# MCU.net
KiCad netlist of a schematic drawn in Altium Designer
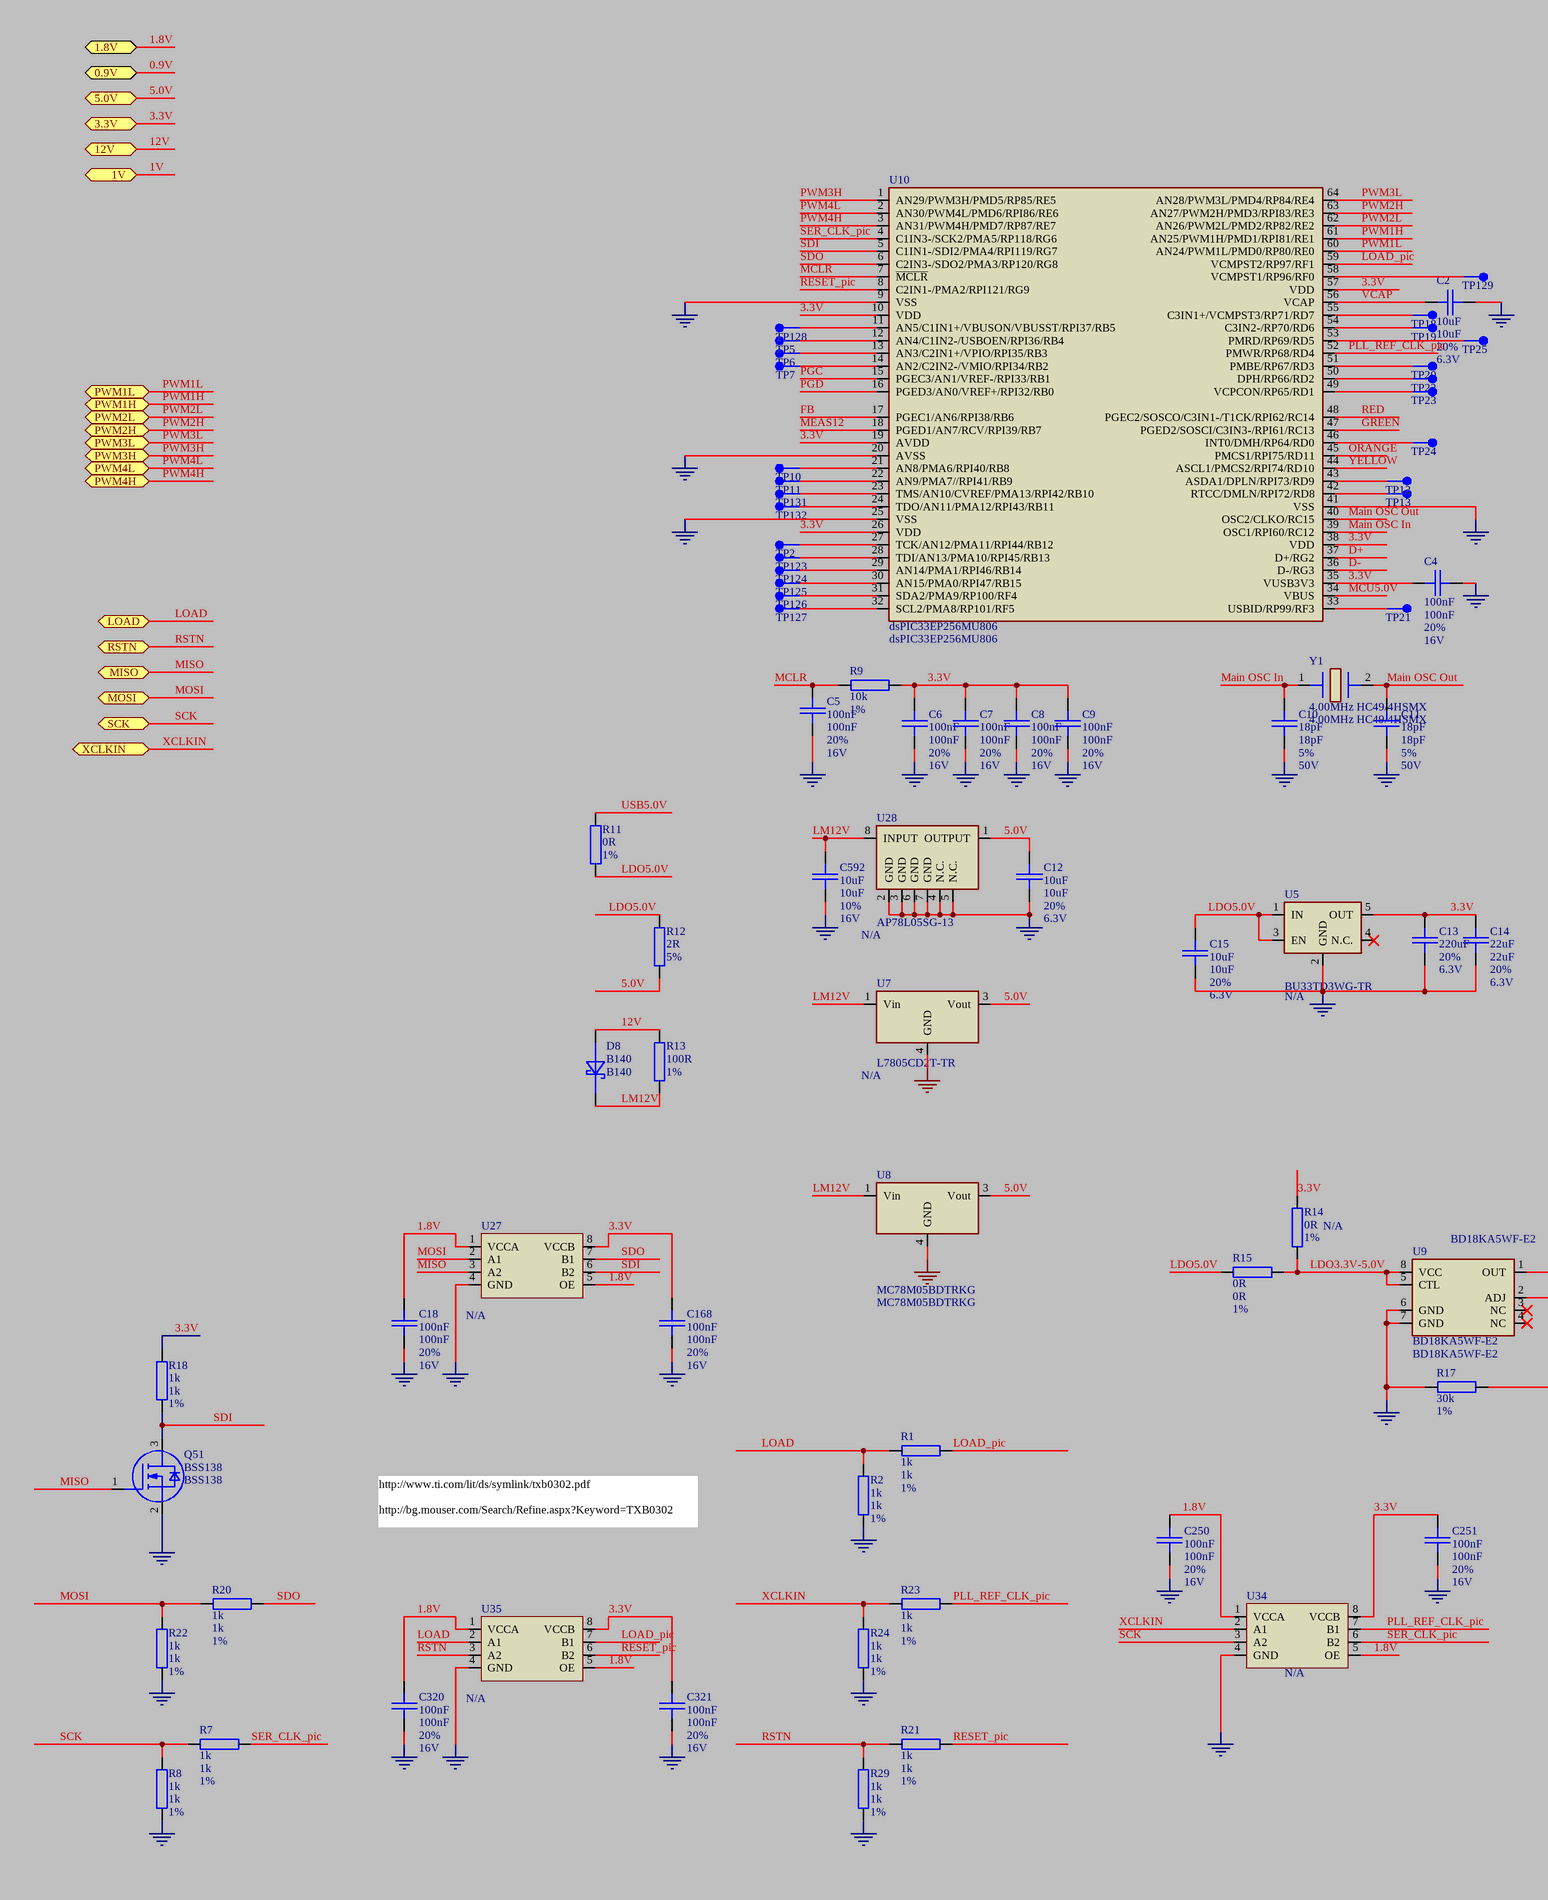
[diagram p0: MCU.SchDoc, left]
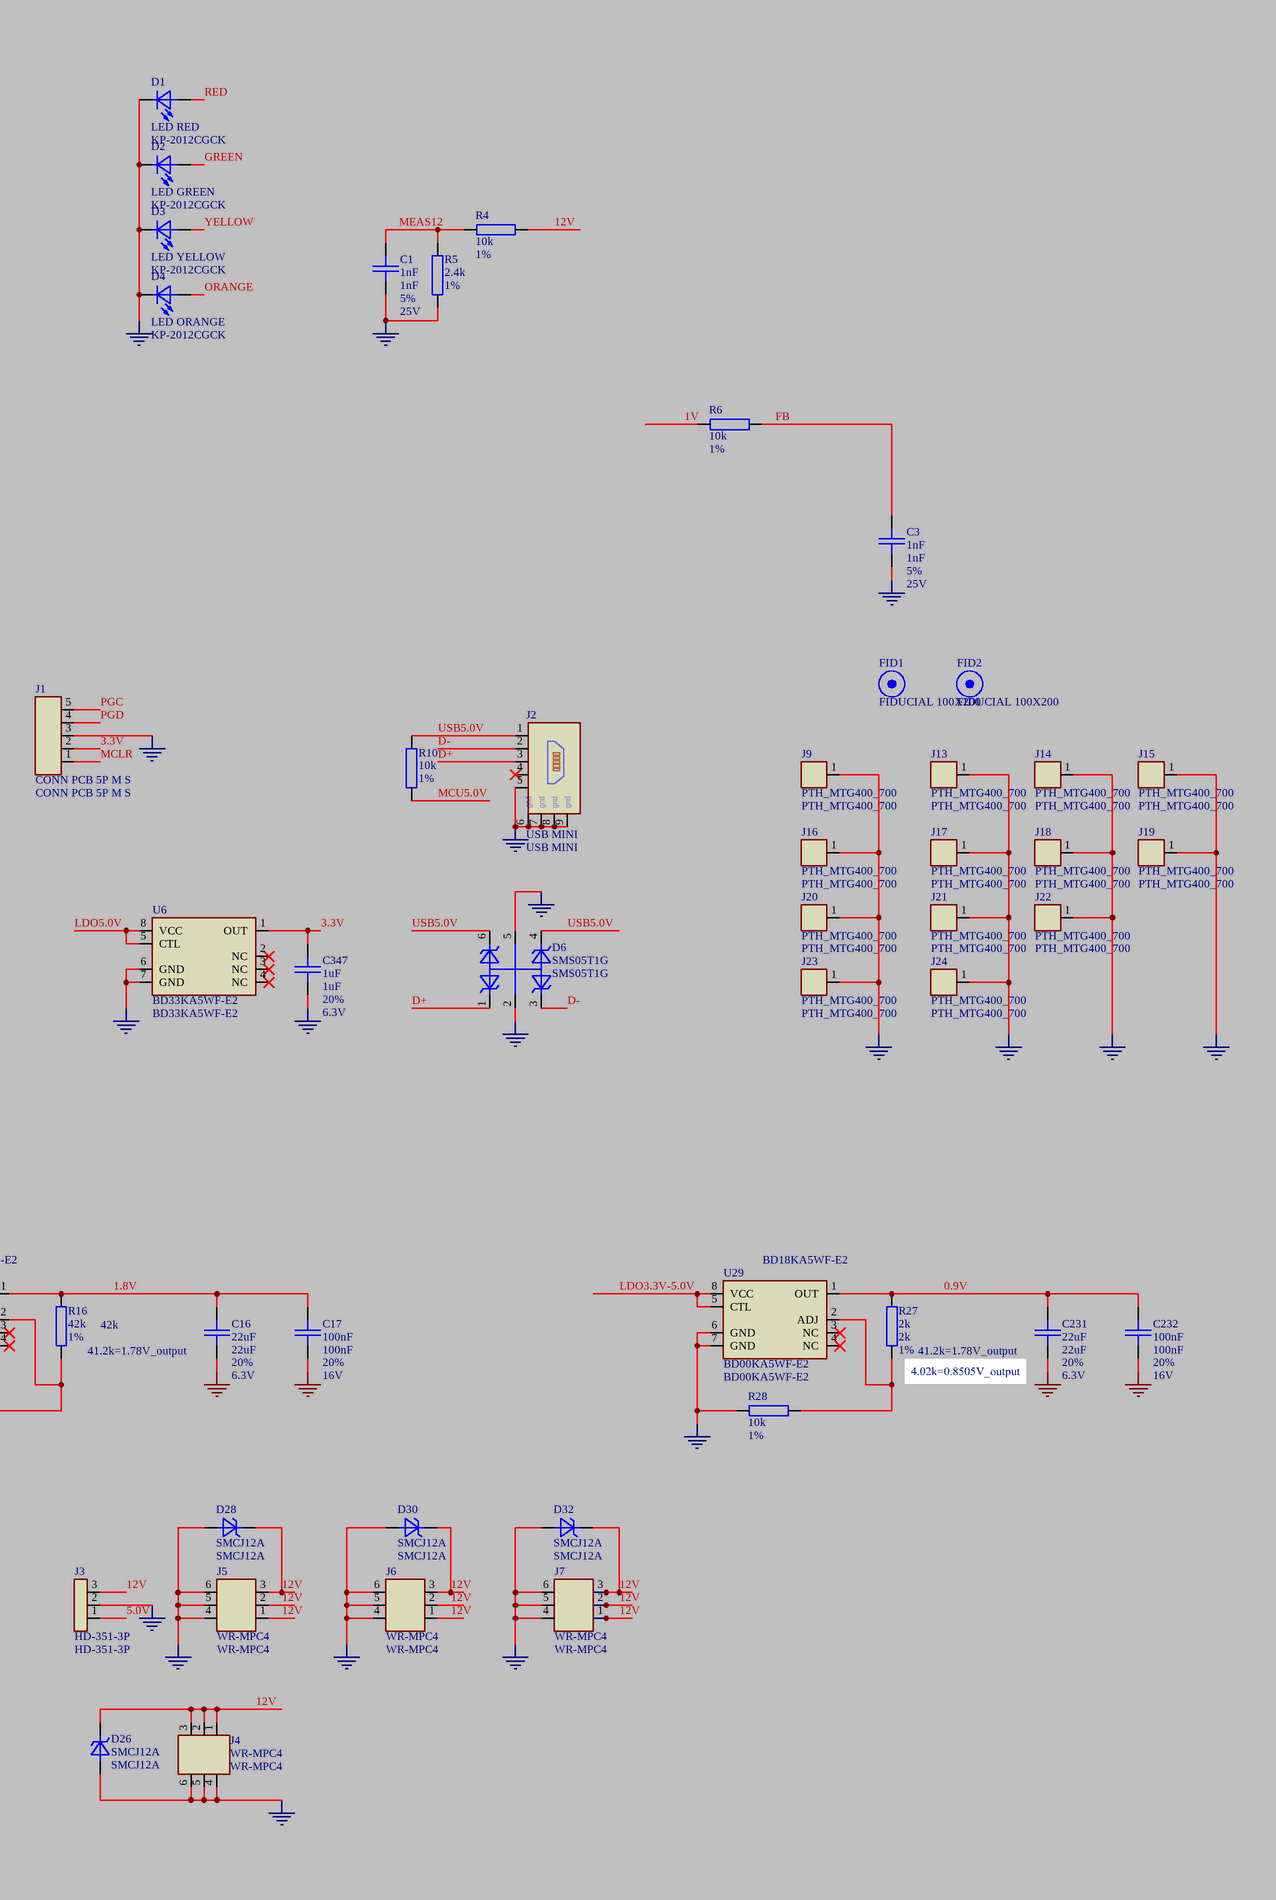
[diagram p1: MCU.SchDoc, right]

(export (version "E")
  (design (tool "Eeschema 10.0.6"))
  (components
    (comp (ref "C1")
      (value "1nF")
      (footprint "SMD_0603_CAPC1608X95N")
      (fields
        (field (name "DB_PART_NUMBER") "CAP000024113")
        (field (name "DB_VALUE") "1nF")
        (field (name "DB_TOLERANCE") "5%")
        (field (name "DB_VOLTAGE") "25V")
        (field (name "DB_MANUFACTURER_PART") "KEMET    C0603C102J3RAC")
        (field (name "DB_APPROVED_BY") "ISHIDDEN=T")
      )
      (libsource (lib "Database_Libs1") (part "C"))
    )
    (comp (ref "C2")
      (value "10uF")
      (footprint "SMD_0603_CAPC1608X95N")
      (fields
        (field (name "DB_PART_NUMBER") "CAP000043646")
        (field (name "DB_VALUE") "10uF")
        (field (name "DB_TOLERANCE") "20%")
        (field (name "DB_VOLTAGE") "6.3V")
        (field (name "DB_MANUFACTURER_PART") "KEMET    C0603C106M9PAC")
        (field (name "DB_APPROVED_BY") "ISHIDDEN=T")
      )
      (libsource (lib "Database_Libs1") (part "C"))
    )
    (comp (ref "C3")
      (value "1nF")
      (footprint "SMD_0603_CAPC1608X95N")
      (fields
        (field (name "DB_PART_NUMBER") "CAP000024113")
        (field (name "DB_VALUE") "1nF")
        (field (name "DB_TOLERANCE") "5%")
        (field (name "DB_VOLTAGE") "25V")
        (field (name "DB_MANUFACTURER_PART") "KEMET    C0603C102J3RAC")
        (field (name "DB_APPROVED_BY") "ISHIDDEN=T")
      )
      (libsource (lib "Database_Libs1") (part "C"))
    )
    (comp (ref "C4")
      (value "100nF")
      (footprint "SMD_0603_CAPC1608X95N")
      (fields
        (field (name "DB_PART_NUMBER") "CAP000027236")
        (field (name "DB_VALUE") "100nF")
        (field (name "DB_TOLERANCE") "20%")
        (field (name "DB_VOLTAGE") "16V")
        (field (name "DB_MANUFACTURER_PART") "KEMET    C0603C104M4RAC")
        (field (name "DB_APPROVED_BY") "ISHIDDEN=T")
      )
      (libsource (lib "Database_Libs1") (part "C"))
    )
    (comp (ref "C5")
      (value "100nF")
      (footprint "SMD_0603_CAPC1608X95N")
      (fields
        (field (name "DB_PART_NUMBER") "CAP000027236")
        (field (name "DB_VALUE") "100nF")
        (field (name "DB_TOLERANCE") "20%")
        (field (name "DB_VOLTAGE") "16V")
        (field (name "DB_MANUFACTURER_PART") "KEMET    C0603C104M4RAC")
        (field (name "DB_APPROVED_BY") "ISHIDDEN=T")
      )
      (libsource (lib "Database_Libs1") (part "C"))
    )
    (comp (ref "C6")
      (value "100nF")
      (footprint "SMD_0603_CAPC1608X95N")
      (fields
        (field (name "DB_PART_NUMBER") "CAP000027236")
        (field (name "DB_VALUE") "100nF")
        (field (name "DB_TOLERANCE") "20%")
        (field (name "DB_VOLTAGE") "16V")
        (field (name "DB_MANUFACTURER_PART") "KEMET    C0603C104M4RAC")
        (field (name "DB_APPROVED_BY") "ISHIDDEN=T")
      )
      (libsource (lib "Database_Libs1") (part "C"))
    )
    (comp (ref "C7")
      (value "100nF")
      (footprint "SMD_0603_CAPC1608X95N")
      (fields
        (field (name "DB_PART_NUMBER") "CAP000027236")
        (field (name "DB_VALUE") "100nF")
        (field (name "DB_TOLERANCE") "20%")
        (field (name "DB_VOLTAGE") "16V")
        (field (name "DB_MANUFACTURER_PART") "KEMET    C0603C104M4RAC")
        (field (name "DB_APPROVED_BY") "ISHIDDEN=T")
      )
      (libsource (lib "Database_Libs1") (part "C"))
    )
    (comp (ref "C8")
      (value "100nF")
      (footprint "SMD_0603_CAPC1608X95N")
      (fields
        (field (name "DB_PART_NUMBER") "CAP000027236")
        (field (name "DB_VALUE") "100nF")
        (field (name "DB_TOLERANCE") "20%")
        (field (name "DB_VOLTAGE") "16V")
        (field (name "DB_MANUFACTURER_PART") "KEMET    C0603C104M4RAC")
        (field (name "DB_APPROVED_BY") "ISHIDDEN=T")
      )
      (libsource (lib "Database_Libs1") (part "C"))
    )
    (comp (ref "C9")
      (value "100nF")
      (footprint "SMD_0603_CAPC1608X95N")
      (fields
        (field (name "DB_PART_NUMBER") "CAP000027236")
        (field (name "DB_VALUE") "100nF")
        (field (name "DB_TOLERANCE") "20%")
        (field (name "DB_VOLTAGE") "16V")
        (field (name "DB_MANUFACTURER_PART") "KEMET    C0603C104M4RAC")
        (field (name "DB_APPROVED_BY") "ISHIDDEN=T")
      )
      (libsource (lib "Database_Libs1") (part "C"))
    )
    (comp (ref "C10")
      (value "18pF")
      (footprint "SMD_0603_CAPC1608X95N")
      (fields
        (field (name "DB_PART_NUMBER") "CAP000031922")
        (field (name "DB_VALUE") "18pF")
        (field (name "DB_TOLERANCE") "5%")
        (field (name "DB_VOLTAGE") "50V")
        (field (name "DB_MANUFACTURER_PART") "KEMET    C0603C180J5GAC")
        (field (name "DB_APPROVED_BY") "ISHIDDEN=T")
      )
      (libsource (lib "Database_Libs1") (part "C"))
    )
    (comp (ref "C11")
      (value "18pF")
      (footprint "SMD_0603_CAPC1608X95N")
      (fields
        (field (name "DB_PART_NUMBER") "CAP000031922")
        (field (name "DB_VALUE") "18pF")
        (field (name "DB_TOLERANCE") "5%")
        (field (name "DB_VOLTAGE") "50V")
        (field (name "DB_MANUFACTURER_PART") "KEMET    C0603C180J5GAC")
        (field (name "DB_APPROVED_BY") "ISHIDDEN=T")
      )
      (libsource (lib "Database_Libs1") (part "C"))
    )
    (comp (ref "C12")
      (value "10uF")
      (footprint "SMD_0603_CAPC1608X95N")
      (fields
        (field (name "DB_PART_NUMBER") "CAP000043646")
        (field (name "DB_VALUE") "10uF")
        (field (name "DB_TOLERANCE") "20%")
        (field (name "DB_VOLTAGE") "6.3V")
        (field (name "DB_MANUFACTURER_PART") "KEMET    C0603C106M9PAC")
        (field (name "DB_APPROVED_BY") "ISHIDDEN=T")
      )
      (libsource (lib "Database_Libs1") (part "C"))
    )
    (comp (ref "C13")
      (value "220uF")
      (footprint "SMD_1210_CAPC3225X279N")
      (fields
        (field (name "DB_PART_NUMBER") "CAP000047355")
        (field (name "DB_VALUE") "220uF")
        (field (name "DB_TOLERANCE") "20%")
        (field (name "DB_VOLTAGE") "6.3V")
        (field (name "DB_MANUFACTURER_PART") "SAMSUNG    CL32A227MQVNNNE")
        (field (name "DB_APPROVED_BY") "VSN")
      )
      (libsource (lib "Database_Libs1") (part "C"))
    )
    (comp (ref "C14")
      (value "22uF")
      (footprint "SMD_0805_CAPC2012X145N")
      (fields
        (field (name "DB_PART_NUMBER") "CAP000043686")
        (field (name "DB_VALUE") "22uF")
        (field (name "DB_TOLERANCE") "20%")
        (field (name "DB_VOLTAGE") "6.3V")
        (field (name "DB_MANUFACTURER_PART") "KEMET    C0805C226M9PAC")
        (field (name "DB_APPROVED_BY") "ISHIDDEN=T")
      )
      (libsource (lib "Database_Libs1") (part "C"))
    )
    (comp (ref "C15")
      (value "10uF")
      (footprint "SMD_0603_CAPC1608X95N")
      (fields
        (field (name "DB_PART_NUMBER") "CAP000043646")
        (field (name "DB_VALUE") "10uF")
        (field (name "DB_TOLERANCE") "20%")
        (field (name "DB_VOLTAGE") "6.3V")
        (field (name "DB_MANUFACTURER_PART") "KEMET    C0603C106M9PAC")
        (field (name "DB_APPROVED_BY") "ISHIDDEN=T")
      )
      (libsource (lib "Database_Libs1") (part "C"))
    )
    (comp (ref "C16")
      (value "22uF")
      (footprint "SMD_0805_CAPC2012X145N")
      (fields
        (field (name "DB_PART_NUMBER") "CAP000043686")
        (field (name "DB_VALUE") "22uF")
        (field (name "DB_TOLERANCE") "20%")
        (field (name "DB_VOLTAGE") "6.3V")
        (field (name "DB_MANUFACTURER_PART") "KEMET    C0805C226M9PAC")
        (field (name "DB_APPROVED_BY") "ISHIDDEN=T")
      )
      (libsource (lib "Database_Libs1") (part "C"))
    )
    (comp (ref "C17")
      (value "100nF")
      (footprint "SMD_0603_CAPC1608X95N")
      (fields
        (field (name "DB_PART_NUMBER") "CAP000027236")
        (field (name "DB_VALUE") "100nF")
        (field (name "DB_TOLERANCE") "20%")
        (field (name "DB_VOLTAGE") "16V")
        (field (name "DB_MANUFACTURER_PART") "KEMET    C0603C104M4RAC")
        (field (name "DB_APPROVED_BY") "ISHIDDEN=T")
      )
      (libsource (lib "Database_Libs1") (part "C"))
    )
    (comp (ref "C18")
      (value "100nF")
      (footprint "SMD_0603_CAPC1608X95N")
      (fields
        (field (name "DB_PART_NUMBER") "CAP000027236")
        (field (name "DB_VALUE") "100nF")
        (field (name "DB_TOLERANCE") "20%")
        (field (name "DB_VOLTAGE") "16V")
        (field (name "DB_MANUFACTURER_PART") "KEMET    C0603C104M4RAC")
        (field (name "DB_APPROVED_BY") "ISHIDDEN=T")
      )
      (libsource (lib "Database_Libs1") (part "C"))
    )
    (comp (ref "C168")
      (value "100nF")
      (footprint "SMD_0603_CAPC1608X95N")
      (fields
        (field (name "DB_PART_NUMBER") "CAP000027236")
        (field (name "DB_VALUE") "100nF")
        (field (name "DB_TOLERANCE") "20%")
        (field (name "DB_VOLTAGE") "16V")
        (field (name "DB_MANUFACTURER_PART") "KEMET    C0603C104M4RAC")
        (field (name "DB_APPROVED_BY") "ISHIDDEN=T")
      )
      (libsource (lib "Database_Libs1") (part "C"))
    )
    (comp (ref "C231")
      (value "22uF")
      (footprint "SMD_0805_CAPC2012X145N")
      (fields
        (field (name "DB_PART_NUMBER") "CAP000043686")
        (field (name "DB_VALUE") "22uF")
        (field (name "DB_TOLERANCE") "20%")
        (field (name "DB_VOLTAGE") "6.3V")
        (field (name "DB_MANUFACTURER_PART") "KEMET    C0805C226M9PAC")
        (field (name "DB_APPROVED_BY") "ISHIDDEN=T")
      )
      (libsource (lib "Database_Libs1") (part "C"))
    )
    (comp (ref "C232")
      (value "100nF")
      (footprint "SMD_0603_CAPC1608X95N")
      (fields
        (field (name "DB_PART_NUMBER") "CAP000027236")
        (field (name "DB_VALUE") "100nF")
        (field (name "DB_TOLERANCE") "20%")
        (field (name "DB_VOLTAGE") "16V")
        (field (name "DB_MANUFACTURER_PART") "KEMET    C0603C104M4RAC")
        (field (name "DB_APPROVED_BY") "ISHIDDEN=T")
      )
      (libsource (lib "Database_Libs1") (part "C"))
    )
    (comp (ref "C250")
      (value "100nF")
      (footprint "SMD_0603_CAPC1608X95N")
      (fields
        (field (name "DB_PART_NUMBER") "CAP000027236")
        (field (name "DB_VALUE") "100nF")
        (field (name "DB_TOLERANCE") "20%")
        (field (name "DB_VOLTAGE") "16V")
        (field (name "DB_MANUFACTURER_PART") "KEMET    C0603C104M4RAC")
        (field (name "DB_APPROVED_BY") "ISHIDDEN=T")
      )
      (libsource (lib "Database_Libs1") (part "C"))
    )
    (comp (ref "C251")
      (value "100nF")
      (footprint "SMD_0603_CAPC1608X95N")
      (fields
        (field (name "DB_PART_NUMBER") "CAP000027236")
        (field (name "DB_VALUE") "100nF")
        (field (name "DB_TOLERANCE") "20%")
        (field (name "DB_VOLTAGE") "16V")
        (field (name "DB_MANUFACTURER_PART") "KEMET    C0603C104M4RAC")
        (field (name "DB_APPROVED_BY") "ISHIDDEN=T")
      )
      (libsource (lib "Database_Libs1") (part "C"))
    )
    (comp (ref "C320")
      (value "100nF")
      (footprint "SMD_0603_CAPC1608X95N")
      (fields
        (field (name "DB_PART_NUMBER") "CAP000027236")
        (field (name "DB_VALUE") "100nF")
        (field (name "DB_TOLERANCE") "20%")
        (field (name "DB_VOLTAGE") "16V")
        (field (name "DB_MANUFACTURER_PART") "KEMET    C0603C104M4RAC")
        (field (name "DB_APPROVED_BY") "ISHIDDEN=T")
      )
      (libsource (lib "Database_Libs1") (part "C"))
    )
    (comp (ref "C321")
      (value "100nF")
      (footprint "SMD_0603_CAPC1608X95N")
      (fields
        (field (name "DB_PART_NUMBER") "CAP000027236")
        (field (name "DB_VALUE") "100nF")
        (field (name "DB_TOLERANCE") "20%")
        (field (name "DB_VOLTAGE") "16V")
        (field (name "DB_MANUFACTURER_PART") "KEMET    C0603C104M4RAC")
        (field (name "DB_APPROVED_BY") "ISHIDDEN=T")
      )
      (libsource (lib "Database_Libs1") (part "C"))
    )
    (comp (ref "C347")
      (value "1uF")
      (footprint "SMD_0603_CAPC1608X95N")
      (fields
        (field (name "DB_PART_NUMBER") "CAP000043344")
        (field (name "DB_VALUE") "1uF")
        (field (name "DB_TOLERANCE") "20%")
        (field (name "DB_VOLTAGE") "6.3V")
        (field (name "DB_MANUFACTURER_PART") "KEMET    C0603C105M9PAC")
        (field (name "DB_APPROVED_BY") "ISHIDDEN=T")
      )
      (libsource (lib "Database_Libs1") (part "C"))
    )
    (comp (ref "C592")
      (value "10uF")
      (footprint "SMD_0805_CAPC2012X145N")
      (fields
        (field (name "DB_PART_NUMBER") "CAP000043636")
        (field (name "DB_VALUE") "10uF")
        (field (name "DB_TOLERANCE") "10%")
        (field (name "DB_VOLTAGE") "16V")
        (field (name "DB_MANUFACTURER_PART") "KEMET    C0805C106K4PAC")
        (field (name "DB_APPROVED_BY") "ISHIDDEN=T")
      )
      (libsource (lib "Database_Libs1") (part "C"))
    )
    (comp (ref "D1")
      (value "LED RED")
      (footprint "SMD_0805_LED2012X100N")
      (fields
        (field (name "DB_PART_NUMBER") "OPT000000096")
        (field (name "DB_VALUE") "KP-2012CGCK")
        (field (name "DB_MANUFACTURER_PART") "KINGBRIGHT       KP-2012CGCK")
        (field (name "DB_APPROVED_BY") "VSN")
      )
      (libsource (lib "Database_Libs1") (part "LED"))
    )
    (comp (ref "D2")
      (value "LED GREEN")
      (footprint "SMD_0805_LED2012X100N")
      (fields
        (field (name "DB_PART_NUMBER") "OPT000000096")
        (field (name "DB_VALUE") "KP-2012CGCK")
        (field (name "DB_MANUFACTURER_PART") "KINGBRIGHT       KP-2012CGCK")
        (field (name "DB_APPROVED_BY") "VSN")
      )
      (libsource (lib "Database_Libs1") (part "LED"))
    )
    (comp (ref "D3")
      (value "LED YELLOW")
      (footprint "SMD_0805_LED2012X100N")
      (fields
        (field (name "DB_PART_NUMBER") "OPT000000096")
        (field (name "DB_VALUE") "KP-2012CGCK")
        (field (name "DB_MANUFACTURER_PART") "KINGBRIGHT       KP-2012CGCK")
        (field (name "DB_APPROVED_BY") "VSN")
      )
      (libsource (lib "Database_Libs1") (part "LED"))
    )
    (comp (ref "D4")
      (value "LED ORANGE")
      (footprint "SMD_0805_LED2012X100N")
      (fields
        (field (name "DB_PART_NUMBER") "OPT000000096")
        (field (name "DB_VALUE") "KP-2012CGCK")
        (field (name "DB_MANUFACTURER_PART") "KINGBRIGHT       KP-2012CGCK")
        (field (name "DB_APPROVED_BY") "VSN")
      )
      (libsource (lib "Database_Libs1") (part "LED"))
    )
    (comp (ref "D6")
      (value "SMS05T1G")
      (footprint "SMD_SOT457_SOT95P275X110-6N")
      (fields
        (field (name "DB_PART_NUMBER") "DDE000002846")
        (field (name "DB_VALUE") "SMS05T1G")
        (field (name "DB_MANUFACTURER_PART") "ON SEMICONDUCTOR        SMS05T1G")
        (field (name "DB_APPROVED_BY") "VSN")
      )
      (libsource (lib "Database_Libs1") (part "D_TVS_QUAD_C1A2C3C4A5C6"))
    )
    (comp (ref "D8")
      (value "B140")
      (footprint "SMD_DO214AC_SMA")
      (fields
        (field (name "DB_PART_NUMBER") "DDE000000580")
        (field (name "DB_VALUE") "B140")
        (field (name "DB_MANUFACTURER_PART") "Diodes        B140")
        (field (name "DB_APPROVED_BY") "ISHIDDEN=T")
      )
      (libsource (lib "Database_Libs1") (part "D_STKY"))
    )
    (comp (ref "D26")
      (value "SMCJ12A")
      (footprint "SMD_DO214AC_SMC")
      (fields
        (field (name "DB_PART_NUMBER") "DDE000001725")
        (field (name "DB_VALUE") "SMCJ12A")
        (field (name "DB_MANUFACTURER_PART") "Diodes        SMCJ12A")
        (field (name "DB_APPROVED_BY") "ISHIDDEN=T")
      )
      (libsource (lib "Database_Libs1") (part "D_TVS_UNI"))
    )
    (comp (ref "D28")
      (value "SMCJ12A")
      (footprint "SMD_DO214AC_SMC")
      (fields
        (field (name "DB_PART_NUMBER") "DDE000001725")
        (field (name "DB_VALUE") "SMCJ12A")
        (field (name "DB_MANUFACTURER_PART") "Diodes        SMCJ12A")
        (field (name "DB_APPROVED_BY") "ISHIDDEN=T")
      )
      (libsource (lib "Database_Libs1") (part "D_TVS_UNI"))
    )
    (comp (ref "D30")
      (value "SMCJ12A")
      (footprint "SMD_DO214AC_SMC")
      (fields
        (field (name "DB_PART_NUMBER") "DDE000001725")
        (field (name "DB_VALUE") "SMCJ12A")
        (field (name "DB_MANUFACTURER_PART") "Diodes        SMCJ12A")
        (field (name "DB_APPROVED_BY") "ISHIDDEN=T")
      )
      (libsource (lib "Database_Libs1") (part "D_TVS_UNI"))
    )
    (comp (ref "D32")
      (value "SMCJ12A")
      (footprint "SMD_DO214AC_SMC")
      (fields
        (field (name "DB_PART_NUMBER") "DDE000001725")
        (field (name "DB_VALUE") "SMCJ12A")
        (field (name "DB_MANUFACTURER_PART") "Diodes        SMCJ12A")
        (field (name "DB_APPROVED_BY") "ISHIDDEN=T")
      )
      (libsource (lib "Database_Libs1") (part "D_TVS_UNI"))
    )
    (comp (ref "FID1")
      (value "FIDUCIAL 100X200")
      (footprint "FID100X200")
      (fields
        (field (name "DB_PART_NUMBER") "FID000000001")
        (field (name "DB_MANUFACTURER_PART") "ISHIDDEN=T")
        (field (name "DB_APPROVED_BY") "ISHIDDEN=T")
      )
      (libsource (lib "Database_Libs1") (part "FIDUCIAL"))
    )
    (comp (ref "FID2")
      (value "FIDUCIAL 100X200")
      (footprint "FID100X200")
      (fields
        (field (name "DB_PART_NUMBER") "FID000000001")
        (field (name "DB_MANUFACTURER_PART") "ISHIDDEN=T")
        (field (name "DB_APPROVED_BY") "ISHIDDEN=T")
      )
      (libsource (lib "Database_Libs1") (part "FIDUCIAL"))
    )
    (comp (ref "J1")
      (value "CONN PCB 5P M S")
      (footprint "PTH_HDRV05W64P254_1X05")
      (fields
        (field (name "DB_PART_NUMBER") "CON000000006")
        (field (name "DB_VALUE") "CONN PCB 5P M S")
        (field (name "DB_MANUFACTURER_PART") "W+P        143-12-005-00")
        (field (name "DB_APPROVED_BY") "VSN")
      )
      (libsource (lib "Database_Libs1") (part "CON_5PINS"))
    )
    (comp (ref "J2")
      (value "USB MINI")
      (footprint "SMD_CON-CVILUX-CU04-SCM15B0")
      (fields
        (field (name "DB_PART_NUMBER") "CON000000048")
        (field (name "DB_VALUE") "USB MINI")
        (field (name "DB_MANUFACTURER_PART") "CVILUX       CU04-SCM15B0-R0-LF")
        (field (name "DB_APPROVED_BY") "VSN")
      )
      (libsource (lib "Database_Libs1") (part "CON_USB_MINI_1"))
    )
    (comp (ref "J3")
      (value "HD-351-3P")
      (footprint "PTH_CON_HD-351-3P")
      (fields
        (field (name "DB_PART_NUMBER") "CON000000272")
        (field (name "DB_VALUE") "HD-351-3P")
        (field (name "DB_MANUFACTURER_PART") "HOW DER      HD-351-3P")
        (field (name "DB_APPROVED_BY") "VSN")
      )
      (libsource (lib "Database_Libs1") (part "CON_3PINS"))
    )
    (comp (ref "J4")
      (value "WR-MPC4")
      (footprint "PTH_CON_WR-MRC4-6P")
      (fields
        (field (name "DB_PART_NUMBER") "CON000000271")
        (field (name "DB_VALUE") "WR-MPC4")
        (field (name "DB_MANUFACTURER_PART") "WE         649 006 295 22")
        (field (name "DB_APPROVED_BY") "VSN")
      )
      (libsource (lib "") (part "CON_2ROWS_6PINS_1_1"))
    )
    (comp (ref "J5")
      (value "WR-MPC4")
      (footprint "PTH_CON_WR-MRC4-6P")
      (fields
        (field (name "DB_PART_NUMBER") "CON000000271")
        (field (name "DB_VALUE") "WR-MPC4")
        (field (name "DB_MANUFACTURER_PART") "WE         649 006 295 22")
        (field (name "DB_APPROVED_BY") "VSN")
      )
      (libsource (lib "Database_Libs1") (part "CON_2ROWS_6PINS_1"))
    )
    (comp (ref "J6")
      (value "WR-MPC4")
      (footprint "PTH_CON_WR-MRC4-6P")
      (fields
        (field (name "DB_PART_NUMBER") "CON000000271")
        (field (name "DB_VALUE") "WR-MPC4")
        (field (name "DB_MANUFACTURER_PART") "WE         649 006 295 22")
        (field (name "DB_APPROVED_BY") "VSN")
      )
      (libsource (lib "Database_Libs1") (part "CON_2ROWS_6PINS_1"))
    )
    (comp (ref "J7")
      (value "WR-MPC4")
      (footprint "PTH_CON_WR-MRC4-6P")
      (fields
        (field (name "DB_PART_NUMBER") "CON000000271")
        (field (name "DB_VALUE") "WR-MPC4")
        (field (name "DB_MANUFACTURER_PART") "WE         649 006 295 22")
        (field (name "DB_APPROVED_BY") "VSN")
      )
      (libsource (lib "Database_Libs1") (part "CON_2ROWS_6PINS_1"))
    )
    (comp (ref "J9")
      (value "PTH_MTG400_700")
      (footprint "PTH_MTG400_700")
      (fields
        (field (name "DB_PART_NUMBER") "MTH000000030")
        (field (name "DB_VALUE") "PTH_MTG400_700")
        (field (name "DB_APPROVED_BY") "VSN")
      )
      (libsource (lib "Database_Libs1") (part "CON_1PIN"))
    )
    (comp (ref "J13")
      (value "PTH_MTG400_700")
      (footprint "PTH_MTG400_700")
      (fields
        (field (name "DB_PART_NUMBER") "MTH000000030")
        (field (name "DB_VALUE") "PTH_MTG400_700")
        (field (name "DB_APPROVED_BY") "VSN")
      )
      (libsource (lib "Database_Libs1") (part "CON_1PIN"))
    )
    (comp (ref "J14")
      (value "PTH_MTG400_700")
      (footprint "PTH_MTG400_700")
      (fields
        (field (name "DB_PART_NUMBER") "MTH000000030")
        (field (name "DB_VALUE") "PTH_MTG400_700")
        (field (name "DB_APPROVED_BY") "VSN")
      )
      (libsource (lib "Database_Libs1") (part "CON_1PIN"))
    )
    (comp (ref "J15")
      (value "PTH_MTG400_700")
      (footprint "PTH_MTG400_700")
      (fields
        (field (name "DB_PART_NUMBER") "MTH000000030")
        (field (name "DB_VALUE") "PTH_MTG400_700")
        (field (name "DB_APPROVED_BY") "VSN")
      )
      (libsource (lib "Database_Libs1") (part "CON_1PIN"))
    )
    (comp (ref "J16")
      (value "PTH_MTG400_700")
      (footprint "PTH_MTG400_700")
      (fields
        (field (name "DB_PART_NUMBER") "MTH000000030")
        (field (name "DB_VALUE") "PTH_MTG400_700")
        (field (name "DB_APPROVED_BY") "VSN")
      )
      (libsource (lib "Database_Libs1") (part "CON_1PIN"))
    )
    (comp (ref "J17")
      (value "PTH_MTG400_700")
      (footprint "PTH_MTG400_700")
      (fields
        (field (name "DB_PART_NUMBER") "MTH000000030")
        (field (name "DB_VALUE") "PTH_MTG400_700")
        (field (name "DB_APPROVED_BY") "VSN")
      )
      (libsource (lib "Database_Libs1") (part "CON_1PIN"))
    )
    (comp (ref "J18")
      (value "PTH_MTG400_700")
      (footprint "PTH_MTG400_700")
      (fields
        (field (name "DB_PART_NUMBER") "MTH000000030")
        (field (name "DB_VALUE") "PTH_MTG400_700")
        (field (name "DB_APPROVED_BY") "VSN")
      )
      (libsource (lib "Database_Libs1") (part "CON_1PIN"))
    )
    (comp (ref "J19")
      (value "PTH_MTG400_700")
      (footprint "PTH_MTG400_700")
      (fields
        (field (name "DB_PART_NUMBER") "MTH000000030")
        (field (name "DB_VALUE") "PTH_MTG400_700")
        (field (name "DB_APPROVED_BY") "VSN")
      )
      (libsource (lib "Database_Libs1") (part "CON_1PIN"))
    )
    (comp (ref "J20")
      (value "PTH_MTG400_700")
      (footprint "PTH_MTG400_700")
      (fields
        (field (name "DB_PART_NUMBER") "MTH000000030")
        (field (name "DB_VALUE") "PTH_MTG400_700")
        (field (name "DB_APPROVED_BY") "VSN")
      )
      (libsource (lib "Database_Libs1") (part "CON_1PIN"))
    )
    (comp (ref "J21")
      (value "PTH_MTG400_700")
      (footprint "PTH_MTG400_700")
      (fields
        (field (name "DB_PART_NUMBER") "MTH000000030")
        (field (name "DB_VALUE") "PTH_MTG400_700")
        (field (name "DB_APPROVED_BY") "VSN")
      )
      (libsource (lib "Database_Libs1") (part "CON_1PIN"))
    )
    (comp (ref "J22")
      (value "PTH_MTG400_700")
      (footprint "PTH_MTG400_700")
      (fields
        (field (name "DB_PART_NUMBER") "MTH000000030")
        (field (name "DB_VALUE") "PTH_MTG400_700")
        (field (name "DB_APPROVED_BY") "VSN")
      )
      (libsource (lib "Database_Libs1") (part "CON_1PIN"))
    )
    (comp (ref "J23")
      (value "PTH_MTG400_700")
      (footprint "PTH_MTG400_700")
      (fields
        (field (name "DB_PART_NUMBER") "MTH000000030")
        (field (name "DB_VALUE") "PTH_MTG400_700")
        (field (name "DB_APPROVED_BY") "VSN")
      )
      (libsource (lib "Database_Libs1") (part "CON_1PIN"))
    )
    (comp (ref "J24")
      (value "PTH_MTG400_700")
      (footprint "PTH_MTG400_700")
      (fields
        (field (name "DB_PART_NUMBER") "MTH000000030")
        (field (name "DB_VALUE") "PTH_MTG400_700")
        (field (name "DB_APPROVED_BY") "VSN")
      )
      (libsource (lib "Database_Libs1") (part "CON_1PIN"))
    )
    (comp (ref "Q51")
      (value "BSS138")
      (footprint "SMD_SOT23_SOT95P240X112-3N")
      (fields
        (field (name "DB_PART_NUMBER") "TRA000001460")
        (field (name "DB_VALUE") "BSS138")
        (field (name "DB_MANUFACTURER_PART") "FAIRCHILD        BSS138LT1G")
        (field (name "DB_APPROVED_BY") "VSN")
      )
      (libsource (lib "Database_Libs1") (part "MOS_N_D1_G1S2D3"))
    )
    (comp (ref "R1")
      (value "1k")
      (footprint "SMD_0603_RESC1608X55N")
      (fields
        (field (name "DB_PART_NUMBER") "RES000006252")
        (field (name "DB_VALUE") "1k")
        (field (name "DB_TOLERANCE") "1%")
        (field (name "DB_MANUFACTURER_PART") "YAGEO    RC0603FR-071K")
        (field (name "DB_APPROVED_BY") "ISHIDDEN=T")
      )
      (libsource (lib "Database_Libs1") (part "R"))
    )
    (comp (ref "R2")
      (value "1k")
      (footprint "SMD_0603_RESC1608X55N")
      (fields
        (field (name "DB_PART_NUMBER") "RES000006252")
        (field (name "DB_VALUE") "1k")
        (field (name "DB_TOLERANCE") "1%")
        (field (name "DB_MANUFACTURER_PART") "YAGEO    RC0603FR-071K")
        (field (name "DB_APPROVED_BY") "ISHIDDEN=T")
      )
      (libsource (lib "Database_Libs1") (part "R"))
    )
    (comp (ref "R4")
      (value "10k")
      (footprint "SMD_0603_RESC1608X55N")
      (fields
        (field (name "DB_PART_NUMBER") "RES000008663")
        (field (name "DB_VALUE") "10k")
        (field (name "DB_TOLERANCE") "1%")
        (field (name "DB_MANUFACTURER_PART") "YAGEO    RC0603FR-0710KL")
        (field (name "DB_APPROVED_BY") "VSN")
      )
      (libsource (lib "Database_Libs1") (part "R"))
    )
    (comp (ref "R5")
      (value "2.4k")
      (footprint "SMD_0603_RESC1608X55N")
      (fields
        (field (name "DB_PART_NUMBER") "RES000006261")
        (field (name "DB_VALUE") "2.4k")
        (field (name "DB_TOLERANCE") "1%")
        (field (name "DB_MANUFACTURER_PART") "YAGEO    RC0603FR-072K4")
        (field (name "DB_APPROVED_BY") "ISHIDDEN=T")
      )
      (libsource (lib "Database_Libs1") (part "R"))
    )
    (comp (ref "R6")
      (value "10k")
      (footprint "SMD_0603_RESC1608X55N")
      (fields
        (field (name "DB_PART_NUMBER") "RES000008663")
        (field (name "DB_VALUE") "10k")
        (field (name "DB_TOLERANCE") "1%")
        (field (name "DB_MANUFACTURER_PART") "YAGEO    RC0603FR-0710KL")
        (field (name "DB_APPROVED_BY") "VSN")
      )
      (libsource (lib "Database_Libs1") (part "R"))
    )
    (comp (ref "R7")
      (value "1k")
      (footprint "SMD_0603_RESC1608X55N")
      (fields
        (field (name "DB_PART_NUMBER") "RES000006252")
        (field (name "DB_VALUE") "1k")
        (field (name "DB_TOLERANCE") "1%")
        (field (name "DB_MANUFACTURER_PART") "YAGEO    RC0603FR-071K")
        (field (name "DB_APPROVED_BY") "ISHIDDEN=T")
      )
      (libsource (lib "Database_Libs1") (part "R"))
    )
    (comp (ref "R8")
      (value "1k")
      (footprint "SMD_0603_RESC1608X55N")
      (fields
        (field (name "DB_PART_NUMBER") "RES000006252")
        (field (name "DB_VALUE") "1k")
        (field (name "DB_TOLERANCE") "1%")
        (field (name "DB_MANUFACTURER_PART") "YAGEO    RC0603FR-071K")
        (field (name "DB_APPROVED_BY") "ISHIDDEN=T")
      )
      (libsource (lib "Database_Libs1") (part "R"))
    )
    (comp (ref "R9")
      (value "10k")
      (footprint "SMD_0603_RESC1608X55N")
      (fields
        (field (name "DB_PART_NUMBER") "RES000008663")
        (field (name "DB_VALUE") "10k")
        (field (name "DB_TOLERANCE") "1%")
        (field (name "DB_MANUFACTURER_PART") "YAGEO    RC0603FR-0710KL")
        (field (name "DB_APPROVED_BY") "VSN")
      )
      (libsource (lib "Database_Libs1") (part "R"))
    )
    (comp (ref "R10")
      (value "10k")
      (footprint "SMD_0603_RESC1608X55N")
      (fields
        (field (name "DB_PART_NUMBER") "RES000008663")
        (field (name "DB_VALUE") "10k")
        (field (name "DB_TOLERANCE") "1%")
        (field (name "DB_MANUFACTURER_PART") "YAGEO    RC0603FR-0710KL")
        (field (name "DB_APPROVED_BY") "VSN")
      )
      (libsource (lib "Database_Libs1") (part "R"))
    )
    (comp (ref "R11")
      (value "0R")
      (footprint "SMD_0603_RESC1608X55N")
      (fields
        (field (name "DB_PART_NUMBER") "RES000008926")
        (field (name "DB_VALUE") "0R")
        (field (name "DB_TOLERANCE") "1%")
        (field (name "DB_MANUFACTURER_PART") "YAGEO    AC0603FR-070RL")
        (field (name "DB_APPROVED_BY") "VSN")
      )
      (libsource (lib "Database_Libs1") (part "R"))
    )
    (comp (ref "R12")
      (value "2R")
      (footprint "SMD_1206_RESC3216X65N")
      (fields
        (field (name "DB_PART_NUMBER") "RES000007051")
        (field (name "DB_VALUE") "2R")
        (field (name "DB_TOLERANCE") "5%")
        (field (name "DB_MANUFACTURER_PART") "YAGEO    RC1206JR-072R")
        (field (name "DB_APPROVED_BY") "ISHIDDEN=T")
      )
      (libsource (lib "Database_Libs1") (part "R"))
    )
    (comp (ref "R13")
      (value "100R")
      (footprint "SMD_1206_RESC3216X65N")
      (fields
        (field (name "DB_PART_NUMBER") "RES000006922")
        (field (name "DB_VALUE") "100R")
        (field (name "DB_TOLERANCE") "1%")
        (field (name "DB_MANUFACTURER_PART") "YAGEO    RC1206FR-07100R")
        (field (name "DB_APPROVED_BY") "ISHIDDEN=T")
      )
      (libsource (lib "Database_Libs1") (part "R"))
    )
    (comp (ref "R14")
      (value "0R")
      (footprint "SMD_1206_RESC3216X65N")
      (fields
        (field (name "DB_PART_NUMBER") "RES000008756")
        (field (name "DB_VALUE") "0R")
        (field (name "DB_TOLERANCE") "1%")
        (field (name "DB_MANUFACTURER_PART") "YAGEO    AC1206FR-070RL")
        (field (name "ASSEMBLY") "N/A")
        (field (name "DB_APPROVED_BY") "VSN")
      )
      (libsource (lib "Database_Libs1") (part "R"))
    )
    (comp (ref "R15")
      (value "0R")
      (footprint "SMD_1206_RESC3216X65N")
      (fields
        (field (name "DB_PART_NUMBER") "RES000008756")
        (field (name "DB_VALUE") "0R")
        (field (name "DB_TOLERANCE") "1%")
        (field (name "DB_MANUFACTURER_PART") "YAGEO    AC1206FR-070RL")
        (field (name "DB_APPROVED_BY") "VSN")
      )
      (libsource (lib "Database_Libs1") (part "R"))
    )
    (comp (ref "R16")
      (value "42k")
      (footprint "SMD_0603_RESC1608X55N")
      (fields
        (field (name "DB_VALUE") "42k")
        (field (name "DB_TOLERANCE") "1%")
        (field (name "DB_MANUFACTURER_PART") "YAGEO    RC0603FR-0741K2")
        (field (name "DB_APPROVED_BY") "ISHIDDEN=T")
      )
      (libsource (lib "Database_Libs1") (part "R"))
    )
    (comp (ref "R17")
      (value "30k")
      (footprint "SMD_0603_RESC1608X55N")
      (fields
        (field (name "DB_PART_NUMBER") "RES000006287")
        (field (name "DB_VALUE") "30k")
        (field (name "DB_TOLERANCE") "1%")
        (field (name "DB_MANUFACTURER_PART") "YAGEO    RC0603FR-0730K")
        (field (name "DB_APPROVED_BY") "ISHIDDEN=T")
      )
      (libsource (lib "Database_Libs1") (part "R"))
    )
    (comp (ref "R18")
      (value "1k")
      (footprint "SMD_0603_RESC1608X55N")
      (fields
        (field (name "DB_PART_NUMBER") "RES000006252")
        (field (name "DB_VALUE") "1k")
        (field (name "DB_TOLERANCE") "1%")
        (field (name "DB_MANUFACTURER_PART") "YAGEO    RC0603FR-071K")
        (field (name "DB_APPROVED_BY") "ISHIDDEN=T")
      )
      (libsource (lib "Database_Libs1") (part "R"))
    )
    (comp (ref "R20")
      (value "1k")
      (footprint "SMD_0603_RESC1608X55N")
      (fields
        (field (name "DB_PART_NUMBER") "RES000006252")
        (field (name "DB_VALUE") "1k")
        (field (name "DB_TOLERANCE") "1%")
        (field (name "DB_MANUFACTURER_PART") "YAGEO    RC0603FR-071K")
        (field (name "DB_APPROVED_BY") "ISHIDDEN=T")
      )
      (libsource (lib "Database_Libs1") (part "R"))
    )
    (comp (ref "R21")
      (value "1k")
      (footprint "SMD_0603_RESC1608X55N")
      (fields
        (field (name "DB_PART_NUMBER") "RES000006252")
        (field (name "DB_VALUE") "1k")
        (field (name "DB_TOLERANCE") "1%")
        (field (name "DB_MANUFACTURER_PART") "YAGEO    RC0603FR-071K")
        (field (name "DB_APPROVED_BY") "ISHIDDEN=T")
      )
      (libsource (lib "Database_Libs1") (part "R"))
    )
    (comp (ref "R22")
      (value "1k")
      (footprint "SMD_0603_RESC1608X55N")
      (fields
        (field (name "DB_PART_NUMBER") "RES000006252")
        (field (name "DB_VALUE") "1k")
        (field (name "DB_TOLERANCE") "1%")
        (field (name "DB_MANUFACTURER_PART") "YAGEO    RC0603FR-071K")
        (field (name "DB_APPROVED_BY") "ISHIDDEN=T")
      )
      (libsource (lib "Database_Libs1") (part "R"))
    )
    (comp (ref "R23")
      (value "1k")
      (footprint "SMD_0603_RESC1608X55N")
      (fields
        (field (name "DB_PART_NUMBER") "RES000006252")
        (field (name "DB_VALUE") "1k")
        (field (name "DB_TOLERANCE") "1%")
        (field (name "DB_MANUFACTURER_PART") "YAGEO    RC0603FR-071K")
        (field (name "DB_APPROVED_BY") "ISHIDDEN=T")
      )
      (libsource (lib "Database_Libs1") (part "R"))
    )
    (comp (ref "R24")
      (value "1k")
      (footprint "SMD_0603_RESC1608X55N")
      (fields
        (field (name "DB_PART_NUMBER") "RES000006252")
        (field (name "DB_VALUE") "1k")
        (field (name "DB_TOLERANCE") "1%")
        (field (name "DB_MANUFACTURER_PART") "YAGEO    RC0603FR-071K")
        (field (name "DB_APPROVED_BY") "ISHIDDEN=T")
      )
      (libsource (lib "Database_Libs1") (part "R"))
    )
    (comp (ref "R27")
      (value "2k")
      (footprint "SMD_0603_RESC1608X55N")
      (fields
        (field (name "DB_PART_NUMBER") "RES000008586")
        (field (name "DB_VALUE") "2k")
        (field (name "DB_TOLERANCE") "1%")
        (field (name "DB_MANUFACTURER_PART") "YAGEO       AC0603FR-072KL")
        (field (name "DB_APPROVED_BY") "VSN")
      )
      (libsource (lib "Database_Libs1") (part "R"))
    )
    (comp (ref "R28")
      (value "10k")
      (footprint "SMD_0603_RESC1608X55N")
      (fields
        (field (name "DB_PART_NUMBER") "RES000008663")
        (field (name "DB_VALUE") "10k")
        (field (name "DB_TOLERANCE") "1%")
        (field (name "DB_MANUFACTURER_PART") "YAGEO    RC0603FR-0710KL")
        (field (name "DB_APPROVED_BY") "VSN")
      )
      (libsource (lib "Database_Libs1") (part "R"))
    )
    (comp (ref "R29")
      (value "1k")
      (footprint "SMD_0603_RESC1608X55N")
      (fields
        (field (name "DB_PART_NUMBER") "RES000006252")
        (field (name "DB_VALUE") "1k")
        (field (name "DB_TOLERANCE") "1%")
        (field (name "DB_MANUFACTURER_PART") "YAGEO    RC0603FR-071K")
        (field (name "DB_APPROVED_BY") "ISHIDDEN=T")
      )
      (libsource (lib "Database_Libs1") (part "R"))
    )
    (comp (ref "TP2")
      (value "100_254")
      (footprint "SMD_TP_100-254")
      (fields
        (field (name "DB_PART_NUMBER") "TPO000000001")
        (field (name "DB_MANUFACTURER_PART") "ISHIDDEN=T")
        (field (name "DB_APPROVED_BY") "ISHIDDEN=T")
      )
      (libsource (lib "Database_Libs1") (part "TEST_POINT_1"))
    )
    (comp (ref "TP5")
      (value "100_254")
      (footprint "SMD_TP_100-254")
      (fields
        (field (name "DB_PART_NUMBER") "TPO000000001")
        (field (name "DB_MANUFACTURER_PART") "ISHIDDEN=T")
        (field (name "DB_APPROVED_BY") "ISHIDDEN=T")
      )
      (libsource (lib "Database_Libs1") (part "TEST_POINT_1"))
    )
    (comp (ref "TP6")
      (value "100_254")
      (footprint "SMD_TP_100-254")
      (fields
        (field (name "DB_PART_NUMBER") "TPO000000001")
        (field (name "DB_MANUFACTURER_PART") "ISHIDDEN=T")
        (field (name "DB_APPROVED_BY") "ISHIDDEN=T")
      )
      (libsource (lib "Database_Libs1") (part "TEST_POINT_1"))
    )
    (comp (ref "TP7")
      (value "100_254")
      (footprint "SMD_TP_100-254")
      (fields
        (field (name "DB_PART_NUMBER") "TPO000000001")
        (field (name "DB_MANUFACTURER_PART") "ISHIDDEN=T")
        (field (name "DB_APPROVED_BY") "ISHIDDEN=T")
      )
      (libsource (lib "Database_Libs1") (part "TEST_POINT_1"))
    )
    (comp (ref "TP10")
      (value "100_254")
      (footprint "SMD_TP_100-254")
      (fields
        (field (name "DB_PART_NUMBER") "TPO000000001")
        (field (name "DB_MANUFACTURER_PART") "ISHIDDEN=T")
        (field (name "DB_APPROVED_BY") "ISHIDDEN=T")
      )
      (libsource (lib "Database_Libs1") (part "TEST_POINT_1"))
    )
    (comp (ref "TP11")
      (value "100_254")
      (footprint "SMD_TP_100-254")
      (fields
        (field (name "DB_PART_NUMBER") "TPO000000001")
        (field (name "DB_MANUFACTURER_PART") "ISHIDDEN=T")
        (field (name "DB_APPROVED_BY") "ISHIDDEN=T")
      )
      (libsource (lib "Database_Libs1") (part "TEST_POINT_1"))
    )
    (comp (ref "TP12")
      (value "100_254")
      (footprint "SMD_TP_100-254")
      (fields
        (field (name "DB_PART_NUMBER") "TPO000000001")
        (field (name "DB_MANUFACTURER_PART") "ISHIDDEN=T")
        (field (name "DB_APPROVED_BY") "ISHIDDEN=T")
      )
      (libsource (lib "Database_Libs1") (part "TEST_POINT_1"))
    )
    (comp (ref "TP13")
      (value "100_254")
      (footprint "SMD_TP_100-254")
      (fields
        (field (name "DB_PART_NUMBER") "TPO000000001")
        (field (name "DB_MANUFACTURER_PART") "ISHIDDEN=T")
        (field (name "DB_APPROVED_BY") "ISHIDDEN=T")
      )
      (libsource (lib "Database_Libs1") (part "TEST_POINT_1"))
    )
    (comp (ref "TP18")
      (value "100_254")
      (footprint "SMD_TP_100-254")
      (fields
        (field (name "DB_PART_NUMBER") "TPO000000001")
        (field (name "DB_MANUFACTURER_PART") "ISHIDDEN=T")
        (field (name "DB_APPROVED_BY") "ISHIDDEN=T")
      )
      (libsource (lib "Database_Libs1") (part "TEST_POINT_1"))
    )
    (comp (ref "TP19")
      (value "100_254")
      (footprint "SMD_TP_100-254")
      (fields
        (field (name "DB_PART_NUMBER") "TPO000000001")
        (field (name "DB_MANUFACTURER_PART") "ISHIDDEN=T")
        (field (name "DB_APPROVED_BY") "ISHIDDEN=T")
      )
      (libsource (lib "Database_Libs1") (part "TEST_POINT_1"))
    )
    (comp (ref "TP20")
      (value "100_254")
      (footprint "SMD_TP_100-254")
      (fields
        (field (name "DB_PART_NUMBER") "TPO000000001")
        (field (name "DB_MANUFACTURER_PART") "ISHIDDEN=T")
        (field (name "DB_APPROVED_BY") "ISHIDDEN=T")
      )
      (libsource (lib "Database_Libs1") (part "TEST_POINT_1"))
    )
    (comp (ref "TP21")
      (value "100_254")
      (footprint "SMD_TP_100-254")
      (fields
        (field (name "DB_PART_NUMBER") "TPO000000001")
        (field (name "DB_MANUFACTURER_PART") "ISHIDDEN=T")
        (field (name "DB_APPROVED_BY") "ISHIDDEN=T")
      )
      (libsource (lib "Database_Libs1") (part "TEST_POINT_1"))
    )
    (comp (ref "TP22")
      (value "100_254")
      (footprint "SMD_TP_100-254")
      (fields
        (field (name "DB_PART_NUMBER") "TPO000000001")
        (field (name "DB_MANUFACTURER_PART") "ISHIDDEN=T")
        (field (name "DB_APPROVED_BY") "ISHIDDEN=T")
      )
      (libsource (lib "Database_Libs1") (part "TEST_POINT_1"))
    )
    (comp (ref "TP23")
      (value "100_254")
      (footprint "SMD_TP_100-254")
      (fields
        (field (name "DB_PART_NUMBER") "TPO000000001")
        (field (name "DB_MANUFACTURER_PART") "ISHIDDEN=T")
        (field (name "DB_APPROVED_BY") "ISHIDDEN=T")
      )
      (libsource (lib "Database_Libs1") (part "TEST_POINT_1"))
    )
    (comp (ref "TP24")
      (value "100_254")
      (footprint "SMD_TP_100-254")
      (fields
        (field (name "DB_PART_NUMBER") "TPO000000001")
        (field (name "DB_MANUFACTURER_PART") "ISHIDDEN=T")
        (field (name "DB_APPROVED_BY") "ISHIDDEN=T")
      )
      (libsource (lib "Database_Libs1") (part "TEST_POINT_1"))
    )
    (comp (ref "TP25")
      (value "100_254")
      (footprint "SMD_TP_100-254")
      (fields
        (field (name "DB_PART_NUMBER") "TPO000000001")
        (field (name "DB_MANUFACTURER_PART") "ISHIDDEN=T")
        (field (name "DB_APPROVED_BY") "ISHIDDEN=T")
      )
      (libsource (lib "Database_Libs1") (part "TEST_POINT_1"))
    )
    (comp (ref "TP123")
      (value "100_254")
      (footprint "SMD_TP_100-254")
      (fields
        (field (name "DB_PART_NUMBER") "TPO000000001")
        (field (name "DB_MANUFACTURER_PART") "ISHIDDEN=T")
        (field (name "DB_APPROVED_BY") "ISHIDDEN=T")
      )
      (libsource (lib "Database_Libs1") (part "TEST_POINT_1"))
    )
    (comp (ref "TP124")
      (value "100_254")
      (footprint "SMD_TP_100-254")
      (fields
        (field (name "DB_PART_NUMBER") "TPO000000001")
        (field (name "DB_MANUFACTURER_PART") "ISHIDDEN=T")
        (field (name "DB_APPROVED_BY") "ISHIDDEN=T")
      )
      (libsource (lib "Database_Libs1") (part "TEST_POINT_1"))
    )
    (comp (ref "TP125")
      (value "100_254")
      (footprint "SMD_TP_100-254")
      (fields
        (field (name "DB_PART_NUMBER") "TPO000000001")
        (field (name "DB_MANUFACTURER_PART") "ISHIDDEN=T")
        (field (name "DB_APPROVED_BY") "ISHIDDEN=T")
      )
      (libsource (lib "Database_Libs1") (part "TEST_POINT_1"))
    )
    (comp (ref "TP126")
      (value "100_254")
      (footprint "SMD_TP_100-254")
      (fields
        (field (name "DB_PART_NUMBER") "TPO000000001")
        (field (name "DB_MANUFACTURER_PART") "ISHIDDEN=T")
        (field (name "DB_APPROVED_BY") "ISHIDDEN=T")
      )
      (libsource (lib "Database_Libs1") (part "TEST_POINT_1"))
    )
    (comp (ref "TP127")
      (value "100_254")
      (footprint "SMD_TP_100-254")
      (fields
        (field (name "DB_PART_NUMBER") "TPO000000001")
        (field (name "DB_MANUFACTURER_PART") "ISHIDDEN=T")
        (field (name "DB_APPROVED_BY") "ISHIDDEN=T")
      )
      (libsource (lib "Database_Libs1") (part "TEST_POINT_1"))
    )
    (comp (ref "TP128")
      (value "100_254")
      (footprint "SMD_TP_100-254")
      (fields
        (field (name "DB_PART_NUMBER") "TPO000000001")
        (field (name "DB_MANUFACTURER_PART") "ISHIDDEN=T")
        (field (name "DB_APPROVED_BY") "ISHIDDEN=T")
      )
      (libsource (lib "Database_Libs1") (part "TEST_POINT_1"))
    )
    (comp (ref "TP129")
      (value "100_254")
      (footprint "SMD_TP_100-254")
      (fields
        (field (name "DB_PART_NUMBER") "TPO000000001")
        (field (name "DB_MANUFACTURER_PART") "ISHIDDEN=T")
        (field (name "DB_APPROVED_BY") "ISHIDDEN=T")
      )
      (libsource (lib "Database_Libs1") (part "TEST_POINT_1"))
    )
    (comp (ref "TP131")
      (value "100_254")
      (footprint "SMD_TP_100-254")
      (fields
        (field (name "DB_PART_NUMBER") "TPO000000001")
        (field (name "DB_MANUFACTURER_PART") "ISHIDDEN=T")
        (field (name "DB_APPROVED_BY") "ISHIDDEN=T")
      )
      (libsource (lib "Database_Libs1") (part "TEST_POINT_1"))
    )
    (comp (ref "TP132")
      (value "100_254")
      (footprint "SMD_TP_100-254")
      (fields
        (field (name "DB_PART_NUMBER") "TPO000000001")
        (field (name "DB_MANUFACTURER_PART") "ISHIDDEN=T")
        (field (name "DB_APPROVED_BY") "ISHIDDEN=T")
      )
      (libsource (lib "Database_Libs1") (part "TEST_POINT_1"))
    )
    (comp (ref "U5")
      (value "BU33TD3WG-TR")
      (footprint "SMD_SOT95P280X135-5N")
      (fields
        (field (name "DB_PART_NUMBER") "PSU000000126")
        (field (name "DB_VALUE") "BU33TD3WG-TR")
        (field (name "DB_MANUFACTURER_PART") "ROHM     BU33TD3WG-TR")
        (field (name "ASSEMBLY") "N/A")
        (field (name "DB_APPROVED_BY") "VSN")
      )
      (libsource (lib "Database_Libs1") (part "IC_TLV70033QDDCRQ1"))
    )
    (comp (ref "U6")
      (value "BD33KA5WF-E2")
      (footprint "SMD_SOIC127P620X160-8N")
      (fields
        (field (name "DB_PART_NUMBER") "PSU000000127")
        (field (name "DB_VALUE") "BD33KA5WF-E2")
        (field (name "DB_MANUFACTURER_PART") "ROHM        BD33KA5WF-E2")
        (field (name "DB_APPROVED_BY") "VSN")
      )
      (libsource (lib "Database_Libs1") (part "IC_BDXXKA5WF"))
    )
    (comp (ref "U7")
      (value "L7805CD2T-TR")
      (footprint "SMD_TO254P1542X460-3_4N")
      (fields
        (field (name "DB_PART_NUMBER") "PSU000000129")
        (field (name "DB_VALUE") "L7805CD2T-TR")
        (field (name "DB_MANUFACTURER_PART") "ST       L7805CD2T-TR")
        (field (name "ASSEMBLY") "N/A")
        (field (name "DB_APPROVED_BY") "VSN")
      )
      (libsource (lib "Database_Libs1") (part "IC_IN1OUT3GND4"))
    )
    (comp (ref "U8")
      (value "MC78M05BDTRKG")
      (footprint "SMD_TO229P991X239-4N_DPAK")
      (fields
        (field (name "DB_PART_NUMBER") "PSU000000031")
        (field (name "DB_VALUE") "MC78M05BDTRKG")
        (field (name "DB_MANUFACTURER_PART") "ON Semiconductor       MC78M05BDTRKG")
        (field (name "DB_APPROVED_BY") "VSN")
      )
      (libsource (lib "Database_Libs1") (part "IC_VIN1GND4VOUT3"))
    )
    (comp (ref "U9")
      (value "BD18KA5WF-E2")
      (footprint "SMD_SOIC127P620X160-8N")
      (fields
        (field (name "DB_PART_NUMBER") "PSU000000128")
        (field (name "DB_VALUE") "BD18KA5WF-E2")
        (field (name "DB_MANUFACTURER_PART") "ROHM        BD00KA5WF-E2")
        (field (name "DB_APPROVED_BY") "VSN")
      )
      (libsource (lib "Database_Libs1") (part "IC_BD00KA5WF"))
    )
    (comp (ref "U10")
      (value "dsPIC33EP256MU806")
      (footprint "SMD_QFP50P1200X1200X120-64N")
      (fields
        (field (name "DB_PART_NUMBER") "MCU000000070")
        (field (name "DB_VALUE") "dsPIC33EP256MU806")
        (field (name "DB_MANUFACTURER_PART") "MICROCHIP        DSPIC33EP256MU806-E/PT")
        (field (name "DB_APPROVED_BY") "VSN")
      )
      (libsource (lib "Database_Libs1") (part "IC_DSPIC33EP256MU806-QFN64"))
    )
    (comp (ref "U27")
      (value "~")
      (footprint "SMD_PSON40P120X180X40-8N")
      (fields (field (name "ASSEMBLY") "N/A"))
      (libsource (lib "Schlib1") (part "IC_TXB0302"))
    )
    (comp (ref "U28")
      (value "AP78L05SG-13")
      (footprint "SMD_SOIC127P600X175-8N")
      (fields
        (field (name "DB_PART_NUMBER") "PSU000000125")
        (field (name "DB_VALUE") "AP78L05SG-13")
        (field (name "DB_MANUFACTURER_PART") "DIODES        AP78L05SG-13")
        (field (name "ASSEMBLY") "N/A")
        (field (name "DB_APPROVED_BY") "VSN")
      )
      (libsource (lib "Database_Libs1") (part "IC_LM2931AD-5.0R2G_SO-8"))
    )
    (comp (ref "U29")
      (value "BD00KA5WF-E2")
      (footprint "SMD_SOIC127P620X160-8N")
      (fields
        (field (name "DB_PART_NUMBER") "PSU000000128")
        (field (name "DB_VALUE") "BD00KA5WF-E2")
        (field (name "DB_MANUFACTURER_PART") "ROHM        BD00KA5WF-E2")
        (field (name "DB_APPROVED_BY") "VSN")
      )
      (libsource (lib "Database_Libs1") (part "IC_BD00KA5WF"))
    )
    (comp (ref "U34")
      (value "~")
      (footprint "SMD_PSON40P120X180X40-8N")
      (fields (field (name "ASSEMBLY") "N/A"))
      (libsource (lib "Schlib1") (part "IC_TXB0302"))
    )
    (comp (ref "U35")
      (value "~")
      (footprint "SMD_PSON40P120X180X40-8N")
      (fields (field (name "ASSEMBLY") "N/A"))
      (libsource (lib "Schlib1") (part "IC_TXB0302"))
    )
    (comp (ref "Y1")
      (value "4.00MHz HC49/4HSMX")
      (footprint "SMD_HC49_XTAL1140X480X420N")
      (fields
        (field (name "DB_PART_NUMBER") "OSC000000012")
        (field (name "DB_VALUE") "4.00MHz HC49/4HSMX")
        (field (name "DB_MANUFACTURER_PART") "IQD       4.00MHz HC49/4HSMX")
        (field (name "DB_APPROVED_BY") "VSN")
      )
      (libsource (lib "Database_Libs1") (part "XTAL"))
    )
  )
  (nets
    (net (code "1") (name "/0.9V") (class "Default")
      (node (ref "C231") (pin "1") (pinfunction "1_1") (pintype "passive"))
      (node (ref "C232") (pin "1") (pinfunction "1_1") (pintype "passive"))
      (node (ref "R27") (pin "1") (pinfunction "1_1") (pintype "passive"))
      (node (ref "U29") (pin "1") (pinfunction "OUT_1") (pintype "passive"))
    )
    (net (code "2") (name "/1.8V") (class "Default")
      (node (ref "C16") (pin "1") (pinfunction "1_1") (pintype "passive"))
      (node (ref "C17") (pin "1") (pinfunction "1_1") (pintype "passive"))
      (node (ref "C18") (pin "2") (pinfunction "2_2") (pintype "passive"))
      (node (ref "C250") (pin "2") (pinfunction "2_2") (pintype "passive"))
      (node (ref "C320") (pin "2") (pinfunction "2_2") (pintype "passive"))
      (node (ref "R16") (pin "1") (pinfunction "1_1") (pintype "passive"))
      (node (ref "U27") (pin "1") (pinfunction "VCCA_1") (pintype "passive"))
      (node (ref "U27") (pin "5") (pinfunction "OE_5") (pintype "passive"))
      (node (ref "U34") (pin "1") (pinfunction "VCCA_1") (pintype "passive"))
      (node (ref "U34") (pin "5") (pinfunction "OE_5") (pintype "passive"))
      (node (ref "U35") (pin "1") (pinfunction "VCCA_1") (pintype "passive"))
      (node (ref "U35") (pin "5") (pinfunction "OE_5") (pintype "passive"))
      (node (ref "U9") (pin "1") (pinfunction "OUT_1") (pintype "passive"))
    )
    (net (code "3") (name "/1V") (class "Default")
      (node (ref "R6") (pin "2") (pinfunction "2_2") (pintype "passive"))
    )
    (net (code "4") (name "/3.3V") (class "Default")
      (node (ref "C13") (pin "2") (pinfunction "2_2") (pintype "passive"))
      (node (ref "C14") (pin "1") (pinfunction "1_1") (pintype "passive"))
      (node (ref "C168") (pin "2") (pinfunction "2_2") (pintype "passive"))
      (node (ref "C251") (pin "2") (pinfunction "2_2") (pintype "passive"))
      (node (ref "C321") (pin "2") (pinfunction "2_2") (pintype "passive"))
      (node (ref "C347") (pin "1") (pinfunction "1_1") (pintype "passive"))
      (node (ref "C4") (pin "1") (pinfunction "1_1") (pintype "passive"))
      (node (ref "C6") (pin "1") (pinfunction "1_1") (pintype "passive"))
      (node (ref "C7") (pin "1") (pinfunction "1_1") (pintype "passive"))
      (node (ref "C8") (pin "1") (pinfunction "1_1") (pintype "passive"))
      (node (ref "C9") (pin "1") (pinfunction "1_1") (pintype "passive"))
      (node (ref "J1") (pin "2") (pinfunction "2_2") (pintype "passive"))
      (node (ref "R14") (pin "2") (pinfunction "2_2") (pintype "passive"))
      (node (ref "R18") (pin "1") (pinfunction "1_1") (pintype "passive"))
      (node (ref "R9") (pin "2") (pinfunction "2_2") (pintype "passive"))
      (node (ref "U10") (pin "10") (pinfunction "VDD_10") (pintype "passive"))
      (node (ref "U10") (pin "19") (pinfunction "AVDD_19") (pintype "passive"))
      (node (ref "U10") (pin "26") (pinfunction "VDD_26") (pintype "passive"))
      (node (ref "U10") (pin "35") (pinfunction "VUSB3V3_35") (pintype "passive"))
      (node (ref "U10") (pin "38") (pinfunction "VDD_38") (pintype "passive"))
      (node (ref "U10") (pin "57") (pinfunction "VDD_57") (pintype "passive"))
      (node (ref "U27") (pin "8") (pinfunction "VCCB_8") (pintype "passive"))
      (node (ref "U34") (pin "8") (pinfunction "VCCB_8") (pintype "passive"))
      (node (ref "U35") (pin "8") (pinfunction "VCCB_8") (pintype "passive"))
      (node (ref "U5") (pin "5") (pinfunction "OUT_5") (pintype "passive"))
      (node (ref "U6") (pin "1") (pinfunction "OUT_1") (pintype "passive"))
    )
    (net (code "5") (name "/5.0V") (class "Default")
      (node (ref "C12") (pin "1") (pinfunction "1_1") (pintype "passive"))
      (node (ref "J3") (pin "1") (pinfunction "1_1") (pintype "passive"))
      (node (ref "R12") (pin "1") (pinfunction "1_1") (pintype "passive"))
      (node (ref "U28") (pin "1") (pinfunction "OUTPUT_1") (pintype "passive"))
      (node (ref "U7") (pin "3") (pinfunction "Vout_3") (pintype "passive"))
      (node (ref "U8") (pin "3") (pinfunction "Vout_3") (pintype "passive"))
    )
    (net (code "6") (name "/12V") (class "Default")
      (node (ref "D26") (pin "1") (pinfunction "C_1") (pintype "passive"))
      (node (ref "D28") (pin "1") (pinfunction "C_1") (pintype "passive"))
      (node (ref "D30") (pin "1") (pinfunction "C_1") (pintype "passive"))
      (node (ref "D32") (pin "1") (pinfunction "C_1") (pintype "passive"))
      (node (ref "D8") (pin "2") (pinfunction "A_2") (pintype "passive"))
      (node (ref "J3") (pin "3") (pinfunction "3_3") (pintype "passive"))
      (node (ref "J4") (pin "1") (pinfunction "1_1") (pintype "passive"))
      (node (ref "J4") (pin "2") (pinfunction "2_2") (pintype "passive"))
      (node (ref "J4") (pin "3") (pinfunction "3_3") (pintype "passive"))
      (node (ref "J5") (pin "1") (pinfunction "1_1") (pintype "passive"))
      (node (ref "J5") (pin "2") (pinfunction "2_2") (pintype "passive"))
      (node (ref "J5") (pin "3") (pinfunction "3_3") (pintype "passive"))
      (node (ref "J6") (pin "1") (pinfunction "1_1") (pintype "passive"))
      (node (ref "J6") (pin "2") (pinfunction "2_2") (pintype "passive"))
      (node (ref "J6") (pin "3") (pinfunction "3_3") (pintype "passive"))
      (node (ref "J7") (pin "1") (pinfunction "1_1") (pintype "passive"))
      (node (ref "J7") (pin "2") (pinfunction "2_2") (pintype "passive"))
      (node (ref "J7") (pin "3") (pinfunction "3_3") (pintype "passive"))
      (node (ref "R13") (pin "2") (pinfunction "2_2") (pintype "passive"))
      (node (ref "R4") (pin "1") (pinfunction "1_1") (pintype "passive"))
    )
    (net (code "7") (name "/D+") (class "Default")
      (node (ref "D6") (pin "1") (pinfunction "1_1") (pintype "passive"))
      (node (ref "J2") (pin "3") (pinfunction "3_3") (pintype "passive"))
      (node (ref "U10") (pin "37") (pinfunction "D+/RG2_37") (pintype "passive"))
    )
    (net (code "8") (name "/D-") (class "Default")
      (node (ref "D6") (pin "3") (pinfunction "3_3") (pintype "passive"))
      (node (ref "J2") (pin "2") (pinfunction "2_2") (pintype "passive"))
      (node (ref "U10") (pin "36") (pinfunction "D-/RG3_36") (pintype "passive"))
    )
    (net (code "9") (name "/FB") (class "Default")
      (node (ref "C3") (pin "1") (pinfunction "1_1") (pintype "passive"))
      (node (ref "R6") (pin "1") (pinfunction "1_1") (pintype "passive"))
      (node (ref "U10") (pin "17") (pinfunction "PGEC1/AN6/RPI38/RB6_17") (pintype "passive"))
    )
    (net (code "10") (name "/GREEN") (class "Default")
      (node (ref "D2") (pin "2") (pinfunction "A_2") (pintype "passive"))
      (node (ref "U10") (pin "47") (pinfunction "PGED2/SOSCI/C3IN3-/RPI61/RC13_47") (pintype "passive"))
    )
    (net (code "11") (name "/LDO3.3V-5.0V") (class "Default")
      (node (ref "R14") (pin "1") (pinfunction "1_1") (pintype "passive"))
      (node (ref "R15") (pin "1") (pinfunction "1_1") (pintype "passive"))
      (node (ref "U29") (pin "5") (pinfunction "CTL_5") (pintype "passive"))
      (node (ref "U29") (pin "8") (pinfunction "VCC_8") (pintype "passive"))
      (node (ref "U9") (pin "5") (pinfunction "CTL_5") (pintype "passive"))
      (node (ref "U9") (pin "8") (pinfunction "VCC_8") (pintype "passive"))
    )
    (net (code "12") (name "/LDO5.0V") (class "Default")
      (node (ref "C15") (pin "1") (pinfunction "1_1") (pintype "passive"))
      (node (ref "R11") (pin "1") (pinfunction "1_1") (pintype "passive"))
      (node (ref "R12") (pin "2") (pinfunction "2_2") (pintype "passive"))
      (node (ref "R15") (pin "2") (pinfunction "2_2") (pintype "passive"))
      (node (ref "U5") (pin "1") (pinfunction "IN_1") (pintype "passive"))
      (node (ref "U5") (pin "3") (pinfunction "EN_3") (pintype "passive"))
      (node (ref "U6") (pin "5") (pinfunction "CTL_5") (pintype "passive"))
      (node (ref "U6") (pin "8") (pinfunction "VCC_8") (pintype "passive"))
    )
    (net (code "13") (name "/LM12V") (class "Default")
      (node (ref "C592") (pin "1") (pinfunction "1_1") (pintype "passive"))
      (node (ref "D8") (pin "1") (pinfunction "C_1") (pintype "passive"))
      (node (ref "R13") (pin "1") (pinfunction "1_1") (pintype "passive"))
      (node (ref "U28") (pin "8") (pinfunction "INPUT_8") (pintype "passive"))
      (node (ref "U7") (pin "1") (pinfunction "Vin_1") (pintype "passive"))
      (node (ref "U8") (pin "1") (pinfunction "Vin_1") (pintype "passive"))
    )
    (net (code "14") (name "/LOAD") (class "Default")
      (node (ref "R1") (pin "1") (pinfunction "1_1") (pintype "passive"))
      (node (ref "R2") (pin "1") (pinfunction "1_1") (pintype "passive"))
      (node (ref "U35") (pin "2") (pinfunction "A1_2") (pintype "passive"))
    )
    (net (code "15") (name "/LOAD_pic") (class "Default")
      (node (ref "R1") (pin "2") (pinfunction "2_2") (pintype "passive"))
      (node (ref "U10") (pin "59") (pinfunction "VCMPST2/RP97/RF1_59") (pintype "passive"))
      (node (ref "U35") (pin "7") (pinfunction "B1_7") (pintype "passive"))
    )
    (net (code "16") (name "/MCLR") (class "Default")
      (node (ref "C5") (pin "1") (pinfunction "1_1") (pintype "passive"))
      (node (ref "J1") (pin "1") (pinfunction "1_1") (pintype "passive"))
      (node (ref "R9") (pin "1") (pinfunction "1_1") (pintype "passive"))
      (node (ref "U10") (pin "7") (pinfunction "~{MCLR}_7") (pintype "passive"))
    )
    (net (code "17") (name "/MCU5.0V") (class "Default")
      (node (ref "R10") (pin "2") (pinfunction "2_2") (pintype "passive"))
      (node (ref "U10") (pin "34") (pinfunction "VBUS_34") (pintype "passive"))
    )
    (net (code "18") (name "/MEAS12") (class "Default")
      (node (ref "C1") (pin "1") (pinfunction "1_1") (pintype "passive"))
      (node (ref "R4") (pin "2") (pinfunction "2_2") (pintype "passive"))
      (node (ref "R5") (pin "2") (pinfunction "2_2") (pintype "passive"))
      (node (ref "U10") (pin "18") (pinfunction "PGED1/AN7/RCV/RPI39/RB7_18") (pintype "passive"))
    )
    (net (code "19") (name "/MISO") (class "Default")
      (node (ref "Q51") (pin "1") (pinfunction "G_1") (pintype "passive"))
      (node (ref "U27") (pin "3") (pinfunction "A2_3") (pintype "passive"))
    )
    (net (code "20") (name "/MOSI") (class "Default")
      (node (ref "R20") (pin "1") (pinfunction "1_1") (pintype "passive"))
      (node (ref "R22") (pin "1") (pinfunction "1_1") (pintype "passive"))
      (node (ref "U27") (pin "2") (pinfunction "A1_2") (pintype "passive"))
    )
    (net (code "21") (name "/Main OSC In") (class "Default")
      (node (ref "C10") (pin "1") (pinfunction "1_1") (pintype "passive"))
      (node (ref "U10") (pin "39") (pinfunction "OSC1/RPI60/RC12_39") (pintype "passive"))
      (node (ref "Y1") (pin "1") (pinfunction "1_1") (pintype "passive"))
    )
    (net (code "22") (name "/Main OSC Out") (class "Default")
      (node (ref "C11") (pin "1") (pinfunction "1_1") (pintype "passive"))
      (node (ref "U10") (pin "40") (pinfunction "OSC2/CLKO/RC15_40") (pintype "passive"))
      (node (ref "Y1") (pin "2") (pinfunction "2_2") (pintype "passive"))
    )
    (net (code "23") (name "/ORANGE") (class "Default")
      (node (ref "D4") (pin "2") (pinfunction "A_2") (pintype "passive"))
      (node (ref "U10") (pin "45") (pinfunction "PMCS1/RPI75/RD11_45") (pintype "passive"))
    )
    (net (code "24") (name "/PGC") (class "Default")
      (node (ref "J1") (pin "5") (pinfunction "5_5") (pintype "passive"))
      (node (ref "U10") (pin "15") (pinfunction "PGEC3/AN1/VREF-/RPI33/RB1_15") (pintype "passive"))
    )
    (net (code "25") (name "/PGD") (class "Default")
      (node (ref "J1") (pin "4") (pinfunction "4_4") (pintype "passive"))
      (node (ref "U10") (pin "16") (pinfunction "PGED3/AN0/VREF+/RPI32/RB0_16") (pintype "passive"))
    )
    (net (code "26") (name "/PLL_REF_CLK_pic") (class "Default")
      (node (ref "R23") (pin "2") (pinfunction "2_2") (pintype "passive"))
      (node (ref "U10") (pin "52") (pinfunction "PMWR/RP68/RD4_52") (pintype "passive"))
      (node (ref "U34") (pin "7") (pinfunction "B1_7") (pintype "passive"))
    )
    (net (code "27") (name "/PWM1H") (class "Default")
      (node (ref "U10") (pin "61") (pinfunction "AN25/PWM1H/PMD1/RPI81/RE1_61") (pintype "passive"))
    )
    (net (code "28") (name "/PWM1L") (class "Default")
      (node (ref "U10") (pin "60") (pinfunction "AN24/PWM1L/PMD0/RP80/RE0_60") (pintype "passive"))
    )
    (net (code "29") (name "/PWM2H") (class "Default")
      (node (ref "U10") (pin "63") (pinfunction "AN27/PWM2H/PMD3/RPI83/RE3_63") (pintype "passive"))
    )
    (net (code "30") (name "/PWM2L") (class "Default")
      (node (ref "U10") (pin "62") (pinfunction "AN26/PWM2L/PMD2/RP82/RE2_62") (pintype "passive"))
    )
    (net (code "31") (name "/PWM3H") (class "Default")
      (node (ref "U10") (pin "1") (pinfunction "AN29/PWM3H/PMD5/RP85/RE5_1") (pintype "passive"))
    )
    (net (code "32") (name "/PWM3L") (class "Default")
      (node (ref "U10") (pin "64") (pinfunction "AN28/PWM3L/PMD4/RP84/RE4_64") (pintype "passive"))
    )
    (net (code "33") (name "/PWM4H") (class "Default")
      (node (ref "U10") (pin "3") (pinfunction "AN31/PWM4H/PMD7/RP87/RE7_3") (pintype "passive"))
    )
    (net (code "34") (name "/PWM4L") (class "Default")
      (node (ref "U10") (pin "2") (pinfunction "AN30/PWM4L/PMD6/RPI86/RE6_2") (pintype "passive"))
    )
    (net (code "35") (name "/RED") (class "Default")
      (node (ref "D1") (pin "2") (pinfunction "A_2") (pintype "passive"))
      (node (ref "U10") (pin "48") (pinfunction "PGEC2/SOSCO/C3IN1-/T1CK/RPI62/RC14_48") (pintype "passive"))
    )
    (net (code "36") (name "/RESET_pic") (class "Default")
      (node (ref "R21") (pin "2") (pinfunction "2_2") (pintype "passive"))
      (node (ref "U10") (pin "8") (pinfunction "C2IN1-/PMA2/RPI121/RG9_8") (pintype "passive"))
      (node (ref "U35") (pin "6") (pinfunction "B2_6") (pintype "passive"))
    )
    (net (code "37") (name "/RSTN") (class "Default")
      (node (ref "R21") (pin "1") (pinfunction "1_1") (pintype "passive"))
      (node (ref "R29") (pin "1") (pinfunction "1_1") (pintype "passive"))
      (node (ref "U35") (pin "3") (pinfunction "A2_3") (pintype "passive"))
    )
    (net (code "38") (name "/SCK") (class "Default")
      (node (ref "R7") (pin "1") (pinfunction "1_1") (pintype "passive"))
      (node (ref "R8") (pin "1") (pinfunction "1_1") (pintype "passive"))
      (node (ref "U34") (pin "3") (pinfunction "A2_3") (pintype "passive"))
    )
    (net (code "39") (name "/SDI") (class "Default")
      (node (ref "Q51") (pin "3") (pinfunction "D_3") (pintype "passive"))
      (node (ref "R18") (pin "2") (pinfunction "2_2") (pintype "passive"))
      (node (ref "U10") (pin "5") (pinfunction "C1IN1-/SDI2/PMA4/RPI119/RG7_5") (pintype "passive"))
      (node (ref "U27") (pin "6") (pinfunction "B2_6") (pintype "passive"))
    )
    (net (code "40") (name "/SDO") (class "Default")
      (node (ref "R20") (pin "2") (pinfunction "2_2") (pintype "passive"))
      (node (ref "U10") (pin "6") (pinfunction "C2IN3-/SDO2/PMA3/RP120/RG8_6") (pintype "passive"))
      (node (ref "U27") (pin "7") (pinfunction "B1_7") (pintype "passive"))
    )
    (net (code "41") (name "/SER_CLK_pic") (class "Default")
      (node (ref "R7") (pin "2") (pinfunction "2_2") (pintype "passive"))
      (node (ref "U10") (pin "4") (pinfunction "C1IN3-/SCK2/PMA5/RP118/RG6_4") (pintype "passive"))
      (node (ref "U34") (pin "6") (pinfunction "B2_6") (pintype "passive"))
    )
    (net (code "42") (name "/USB5.0V") (class "Default")
      (node (ref "D6") (pin "4") (pinfunction "4_4") (pintype "passive"))
      (node (ref "D6") (pin "6") (pinfunction "6_6") (pintype "passive"))
      (node (ref "J2") (pin "1") (pinfunction "1_1") (pintype "passive"))
      (node (ref "R10") (pin "1") (pinfunction "1_1") (pintype "passive"))
      (node (ref "R11") (pin "2") (pinfunction "2_2") (pintype "passive"))
    )
    (net (code "43") (name "/VCAP") (class "Default")
      (node (ref "C2") (pin "1") (pinfunction "1_1") (pintype "passive"))
      (node (ref "U10") (pin "56") (pinfunction "VCAP_56") (pintype "passive"))
    )
    (net (code "44") (name "/XCLKIN") (class "Default")
      (node (ref "R23") (pin "1") (pinfunction "1_1") (pintype "passive"))
      (node (ref "R24") (pin "1") (pinfunction "1_1") (pintype "passive"))
      (node (ref "U34") (pin "2") (pinfunction "A1_2") (pintype "passive"))
    )
    (net (code "45") (name "/YELLOW") (class "Default")
      (node (ref "D3") (pin "2") (pinfunction "A_2") (pintype "passive"))
      (node (ref "U10") (pin "44") (pinfunction "ASCL1/PMCS2/RPI74/RD10_44") (pintype "passive"))
    )
    (net (code "46") (name "GND") (class "Default")
      (node (ref "C1") (pin "2") (pinfunction "2_2") (pintype "passive"))
      (node (ref "C10") (pin "2") (pinfunction "2_2") (pintype "passive"))
      (node (ref "C11") (pin "2") (pinfunction "2_2") (pintype "passive"))
      (node (ref "C12") (pin "2") (pinfunction "2_2") (pintype "passive"))
      (node (ref "C13") (pin "1") (pinfunction "1_1") (pintype "passive"))
      (node (ref "C14") (pin "2") (pinfunction "2_2") (pintype "passive"))
      (node (ref "C15") (pin "2") (pinfunction "2_2") (pintype "passive"))
      (node (ref "C16") (pin "2") (pinfunction "2_2") (pintype "passive"))
      (node (ref "C168") (pin "1") (pinfunction "1_1") (pintype "passive"))
      (node (ref "C17") (pin "2") (pinfunction "2_2") (pintype "passive"))
      (node (ref "C18") (pin "1") (pinfunction "1_1") (pintype "passive"))
      (node (ref "C2") (pin "2") (pinfunction "2_2") (pintype "passive"))
      (node (ref "C231") (pin "2") (pinfunction "2_2") (pintype "passive"))
      (node (ref "C232") (pin "2") (pinfunction "2_2") (pintype "passive"))
      (node (ref "C250") (pin "1") (pinfunction "1_1") (pintype "passive"))
      (node (ref "C251") (pin "1") (pinfunction "1_1") (pintype "passive"))
      (node (ref "C3") (pin "2") (pinfunction "2_2") (pintype "passive"))
      (node (ref "C320") (pin "1") (pinfunction "1_1") (pintype "passive"))
      (node (ref "C321") (pin "1") (pinfunction "1_1") (pintype "passive"))
      (node (ref "C347") (pin "2") (pinfunction "2_2") (pintype "passive"))
      (node (ref "C4") (pin "2") (pinfunction "2_2") (pintype "passive"))
      (node (ref "C5") (pin "2") (pinfunction "2_2") (pintype "passive"))
      (node (ref "C592") (pin "2") (pinfunction "2_2") (pintype "passive"))
      (node (ref "C6") (pin "2") (pinfunction "2_2") (pintype "passive"))
      (node (ref "C7") (pin "2") (pinfunction "2_2") (pintype "passive"))
      (node (ref "C8") (pin "2") (pinfunction "2_2") (pintype "passive"))
      (node (ref "C9") (pin "2") (pinfunction "2_2") (pintype "passive"))
      (node (ref "D1") (pin "1") (pinfunction "C_1") (pintype "passive"))
      (node (ref "D2") (pin "1") (pinfunction "C_1") (pintype "passive"))
      (node (ref "D26") (pin "2") (pinfunction "A_2") (pintype "passive"))
      (node (ref "D28") (pin "2") (pinfunction "A_2") (pintype "passive"))
      (node (ref "D3") (pin "1") (pinfunction "C_1") (pintype "passive"))
      (node (ref "D30") (pin "2") (pinfunction "A_2") (pintype "passive"))
      (node (ref "D32") (pin "2") (pinfunction "A_2") (pintype "passive"))
      (node (ref "D4") (pin "1") (pinfunction "C_1") (pintype "passive"))
      (node (ref "D6") (pin "2") (pinfunction "2_2") (pintype "passive"))
      (node (ref "D6") (pin "5") (pinfunction "5_5") (pintype "passive"))
      (node (ref "J1") (pin "3") (pinfunction "3_3") (pintype "passive"))
      (node (ref "J13") (pin "1") (pinfunction "1_1") (pintype "passive"))
      (node (ref "J14") (pin "1") (pinfunction "1_1") (pintype "passive"))
      (node (ref "J15") (pin "1") (pinfunction "1_1") (pintype "passive"))
      (node (ref "J16") (pin "1") (pinfunction "1_1") (pintype "passive"))
      (node (ref "J17") (pin "1") (pinfunction "1_1") (pintype "passive"))
      (node (ref "J18") (pin "1") (pinfunction "1_1") (pintype "passive"))
      (node (ref "J19") (pin "1") (pinfunction "1_1") (pintype "passive"))
      (node (ref "J2") (pin "5") (pinfunction "5_5") (pintype "passive"))
      (node (ref "J2") (pin "6") (pinfunction "6_6") (pintype "passive"))
      (node (ref "J2") (pin "7") (pinfunction "7_7") (pintype "passive"))
      (node (ref "J2") (pin "8") (pinfunction "8_8") (pintype "passive"))
      (node (ref "J2") (pin "9") (pinfunction "9_9") (pintype "passive"))
      (node (ref "J20") (pin "1") (pinfunction "1_1") (pintype "passive"))
      (node (ref "J21") (pin "1") (pinfunction "1_1") (pintype "passive"))
      (node (ref "J22") (pin "1") (pinfunction "1_1") (pintype "passive"))
      (node (ref "J23") (pin "1") (pinfunction "1_1") (pintype "passive"))
      (node (ref "J24") (pin "1") (pinfunction "1_1") (pintype "passive"))
      (node (ref "J3") (pin "2") (pinfunction "2_2") (pintype "passive"))
      (node (ref "J4") (pin "4") (pinfunction "4_4") (pintype "passive"))
      (node (ref "J4") (pin "5") (pinfunction "5_5") (pintype "passive"))
      (node (ref "J4") (pin "6") (pinfunction "6_6") (pintype "passive"))
      (node (ref "J5") (pin "4") (pinfunction "4_4") (pintype "passive"))
      (node (ref "J5") (pin "5") (pinfunction "5_5") (pintype "passive"))
      (node (ref "J5") (pin "6") (pinfunction "6_6") (pintype "passive"))
      (node (ref "J6") (pin "4") (pinfunction "4_4") (pintype "passive"))
      (node (ref "J6") (pin "5") (pinfunction "5_5") (pintype "passive"))
      (node (ref "J6") (pin "6") (pinfunction "6_6") (pintype "passive"))
      (node (ref "J7") (pin "4") (pinfunction "4_4") (pintype "passive"))
      (node (ref "J7") (pin "5") (pinfunction "5_5") (pintype "passive"))
      (node (ref "J7") (pin "6") (pinfunction "6_6") (pintype "passive"))
      (node (ref "J9") (pin "1") (pinfunction "1_1") (pintype "passive"))
      (node (ref "Q51") (pin "2") (pinfunction "S_2") (pintype "passive"))
      (node (ref "R17") (pin "2") (pinfunction "2_2") (pintype "passive"))
      (node (ref "R2") (pin "2") (pinfunction "2_2") (pintype "passive"))
      (node (ref "R22") (pin "2") (pinfunction "2_2") (pintype "passive"))
      (node (ref "R24") (pin "2") (pinfunction "2_2") (pintype "passive"))
      (node (ref "R28") (pin "2") (pinfunction "2_2") (pintype "passive"))
      (node (ref "R29") (pin "2") (pinfunction "2_2") (pintype "passive"))
      (node (ref "R5") (pin "1") (pinfunction "1_1") (pintype "passive"))
      (node (ref "R8") (pin "2") (pinfunction "2_2") (pintype "passive"))
      (node (ref "U10") (pin "20") (pinfunction "AVSS_20") (pintype "passive"))
      (node (ref "U10") (pin "25") (pinfunction "VSS_25") (pintype "passive"))
      (node (ref "U10") (pin "41") (pinfunction "VSS_41") (pintype "passive"))
      (node (ref "U10") (pin "9") (pinfunction "VSS_9") (pintype "passive"))
      (node (ref "U27") (pin "4") (pinfunction "GND_4") (pintype "passive"))
      (node (ref "U28") (pin "2") (pinfunction "GND_2") (pintype "passive"))
      (node (ref "U28") (pin "3") (pinfunction "GND_3") (pintype "passive"))
      (node (ref "U28") (pin "4") (pinfunction "N.C._4") (pintype "passive"))
      (node (ref "U28") (pin "5") (pinfunction "N.C._5") (pintype "passive"))
      (node (ref "U28") (pin "6") (pinfunction "GND_6") (pintype "passive"))
      (node (ref "U28") (pin "7") (pinfunction "GND_7") (pintype "passive"))
      (node (ref "U29") (pin "6") (pinfunction "GND_6") (pintype "passive"))
      (node (ref "U29") (pin "7") (pinfunction "GND_7") (pintype "passive"))
      (node (ref "U34") (pin "4") (pinfunction "GND_4") (pintype "passive"))
      (node (ref "U35") (pin "4") (pinfunction "GND_4") (pintype "passive"))
      (node (ref "U5") (pin "2") (pinfunction "GND_2") (pintype "passive"))
      (node (ref "U6") (pin "6") (pinfunction "GND_6") (pintype "passive"))
      (node (ref "U6") (pin "7") (pinfunction "GND_7") (pintype "passive"))
      (node (ref "U7") (pin "4") (pinfunction "GND_4") (pintype "passive"))
      (node (ref "U8") (pin "4") (pinfunction "GND_4") (pintype "passive"))
      (node (ref "U9") (pin "6") (pinfunction "GND_6") (pintype "passive"))
      (node (ref "U9") (pin "7") (pinfunction "GND_7") (pintype "passive"))
    )
    (net (code "47") (name "Net-(U9-ADJ)") (class "Default")
      (node (ref "R16") (pin "2") (pinfunction "2_2") (pintype "passive"))
      (node (ref "R17") (pin "1") (pinfunction "1_1") (pintype "passive"))
      (node (ref "U9") (pin "2") (pinfunction "ADJ_2") (pintype "passive"))
    )
    (net (code "48") (name "Net-(U10-AN2{slash}C2IN2-{slash}VMIO{slash}RPI34{slash}RB2)") (class "Default")
      (node (ref "TP7") (pin "1") (pinfunction "1_1") (pintype "passive"))
      (node (ref "U10") (pin "14") (pinfunction "AN2/C2IN2-/VMIO/RPI34/RB2_14") (pintype "passive"))
    )
    (net (code "49") (name "Net-(U10-AN3{slash}C2IN1+{slash}VPIO{slash}RPI35{slash}RB3)") (class "Default")
      (node (ref "TP6") (pin "1") (pinfunction "1_1") (pintype "passive"))
      (node (ref "U10") (pin "13") (pinfunction "AN3/C2IN1+/VPIO/RPI35/RB3_13") (pintype "passive"))
    )
    (net (code "50") (name "Net-(U10-AN4{slash}C1IN2-{slash}USBOEN{slash}RPI36{slash}RB4)") (class "Default")
      (node (ref "TP5") (pin "1") (pinfunction "1_1") (pintype "passive"))
      (node (ref "U10") (pin "12") (pinfunction "AN4/C1IN2-/USBOEN/RPI36/RB4_12") (pintype "passive"))
    )
    (net (code "51") (name "Net-(U10-AN5{slash}C1IN1+{slash}VBUSON{slash}VBUSST{slash}RPI37{slash}RB5)") (class "Default")
      (node (ref "TP128") (pin "1") (pinfunction "1_1") (pintype "passive"))
      (node (ref "U10") (pin "11") (pinfunction "AN5/C1IN1+/VBUSON/VBUSST/RPI37/RB5_11") (pintype "passive"))
    )
    (net (code "52") (name "Net-(U10-AN8{slash}PMA6{slash}RPI40{slash}RB8)") (class "Default")
      (node (ref "TP10") (pin "1") (pinfunction "1_1") (pintype "passive"))
      (node (ref "U10") (pin "21") (pinfunction "AN8/PMA6/RPI40/RB8_21") (pintype "passive"))
    )
    (net (code "53") (name "Net-(U10-AN9{slash}PMA7{slash}{slash}RPI41{slash}RB9)") (class "Default")
      (node (ref "TP11") (pin "1") (pinfunction "1_1") (pintype "passive"))
      (node (ref "U10") (pin "22") (pinfunction "AN9/PMA7//RPI41/RB9_22") (pintype "passive"))
    )
    (net (code "54") (name "Net-(U10-AN14{slash}PMA1{slash}RPI46{slash}RB14)") (class "Default")
      (node (ref "TP124") (pin "1") (pinfunction "1_1") (pintype "passive"))
      (node (ref "U10") (pin "29") (pinfunction "AN14/PMA1/RPI46/RB14_29") (pintype "passive"))
    )
    (net (code "55") (name "Net-(U10-AN15{slash}PMA0{slash}RPI47{slash}RB15)") (class "Default")
      (node (ref "TP125") (pin "1") (pinfunction "1_1") (pintype "passive"))
      (node (ref "U10") (pin "30") (pinfunction "AN15/PMA0/RPI47/RB15_30") (pintype "passive"))
    )
    (net (code "56") (name "Net-(U10-ASDA1{slash}DPLN{slash}RPI73{slash}RD9)") (class "Default")
      (node (ref "TP12") (pin "1") (pinfunction "1_1") (pintype "passive"))
      (node (ref "U10") (pin "43") (pinfunction "ASDA1/DPLN/RPI73/RD9_43") (pintype "passive"))
    )
    (net (code "57") (name "Net-(U10-C3IN1+{slash}VCMPST3{slash}RP71{slash}RD7)") (class "Default")
      (node (ref "TP18") (pin "1") (pinfunction "1_1") (pintype "passive"))
      (node (ref "U10") (pin "55") (pinfunction "C3IN1+/VCMPST3/RP71/RD7_55") (pintype "passive"))
    )
    (net (code "58") (name "Net-(U10-C3IN2-{slash}RP70{slash}RD6)") (class "Default")
      (node (ref "TP19") (pin "1") (pinfunction "1_1") (pintype "passive"))
      (node (ref "U10") (pin "54") (pinfunction "C3IN2-/RP70/RD6_54") (pintype "passive"))
    )
    (net (code "59") (name "Net-(U10-DPH{slash}RP66{slash}RD2)") (class "Default")
      (node (ref "TP22") (pin "1") (pinfunction "1_1") (pintype "passive"))
      (node (ref "U10") (pin "50") (pinfunction "DPH/RP66/RD2_50") (pintype "passive"))
    )
    (net (code "60") (name "Net-(U10-INT0{slash}DMH{slash}RP64{slash}RD0)") (class "Default")
      (node (ref "TP24") (pin "1") (pinfunction "1_1") (pintype "passive"))
      (node (ref "U10") (pin "46") (pinfunction "INT0/DMH/RP64/RD0_46") (pintype "passive"))
    )
    (net (code "61") (name "Net-(U10-PMBE{slash}RP67{slash}RD3)") (class "Default")
      (node (ref "TP20") (pin "1") (pinfunction "1_1") (pintype "passive"))
      (node (ref "U10") (pin "51") (pinfunction "PMBE/RP67/RD3_51") (pintype "passive"))
    )
    (net (code "62") (name "Net-(U10-PMRD{slash}RP69{slash}RD5)") (class "Default")
      (node (ref "TP25") (pin "1") (pinfunction "1_1") (pintype "passive"))
      (node (ref "U10") (pin "53") (pinfunction "PMRD/RP69/RD5_53") (pintype "passive"))
    )
    (net (code "63") (name "Net-(U10-RTCC{slash}DMLN{slash}RPI72{slash}RD8)") (class "Default")
      (node (ref "TP13") (pin "1") (pinfunction "1_1") (pintype "passive"))
      (node (ref "U10") (pin "42") (pinfunction "RTCC/DMLN/RPI72/RD8_42") (pintype "passive"))
    )
    (net (code "64") (name "Net-(U10-SCL2{slash}PMA8{slash}RP101{slash}RF5)") (class "Default")
      (node (ref "TP127") (pin "1") (pinfunction "1_1") (pintype "passive"))
      (node (ref "U10") (pin "32") (pinfunction "SCL2/PMA8/RP101/RF5_32") (pintype "passive"))
    )
    (net (code "65") (name "Net-(U10-SDA2{slash}PMA9{slash}RP100{slash}RF4)") (class "Default")
      (node (ref "TP126") (pin "1") (pinfunction "1_1") (pintype "passive"))
      (node (ref "U10") (pin "31") (pinfunction "SDA2/PMA9/RP100/RF4_31") (pintype "passive"))
    )
    (net (code "66") (name "Net-(U10-TCK{slash}AN12{slash}PMA11{slash}RPI44{slash}RB12)") (class "Default")
      (node (ref "TP2") (pin "1") (pinfunction "1_1") (pintype "passive"))
      (node (ref "U10") (pin "27") (pinfunction "TCK/AN12/PMA11/RPI44/RB12_27") (pintype "passive"))
    )
    (net (code "67") (name "Net-(U10-TDI{slash}AN13{slash}PMA10{slash}RPI45{slash}RB13)") (class "Default")
      (node (ref "TP123") (pin "1") (pinfunction "1_1") (pintype "passive"))
      (node (ref "U10") (pin "28") (pinfunction "TDI/AN13/PMA10/RPI45/RB13_28") (pintype "passive"))
    )
    (net (code "68") (name "Net-(U10-TDO{slash}AN11{slash}PMA12{slash}RPI43{slash}RB11)") (class "Default")
      (node (ref "TP132") (pin "1") (pinfunction "1_1") (pintype "passive"))
      (node (ref "U10") (pin "24") (pinfunction "TDO/AN11/PMA12/RPI43/RB11_24") (pintype "passive"))
    )
    (net (code "69") (name "Net-(U10-TMS{slash}AN10{slash}CVREF{slash}PMA13{slash}RPI42{slash}RB10)") (class "Default")
      (node (ref "TP131") (pin "1") (pinfunction "1_1") (pintype "passive"))
      (node (ref "U10") (pin "23") (pinfunction "TMS/AN10/CVREF/PMA13/RPI42/RB10_23") (pintype "passive"))
    )
    (net (code "70") (name "Net-(U10-USBID{slash}RP99{slash}RF3)") (class "Default")
      (node (ref "TP21") (pin "1") (pinfunction "1_1") (pintype "passive"))
      (node (ref "U10") (pin "33") (pinfunction "USBID/RP99/RF3_33") (pintype "passive"))
    )
    (net (code "71") (name "Net-(U10-VCMPST1{slash}RP96{slash}RF0)") (class "Default")
      (node (ref "TP129") (pin "1") (pinfunction "1_1") (pintype "passive"))
      (node (ref "U10") (pin "58") (pinfunction "VCMPST1/RP96/RF0_58") (pintype "passive"))
    )
    (net (code "72") (name "Net-(U10-VCPCON{slash}RP65{slash}RD1)") (class "Default")
      (node (ref "TP23") (pin "1") (pinfunction "1_1") (pintype "passive"))
      (node (ref "U10") (pin "49") (pinfunction "VCPCON/RP65/RD1_49") (pintype "passive"))
    )
    (net (code "73") (name "Net-(U29-ADJ)") (class "Default")
      (node (ref "R27") (pin "2") (pinfunction "2_2") (pintype "passive"))
      (node (ref "R28") (pin "1") (pinfunction "1_1") (pintype "passive"))
      (node (ref "U29") (pin "2") (pinfunction "ADJ_2") (pintype "passive"))
    )
    (net (code "74") (name "unconnected-(J2-Pad4)") (class "Default")
      (node (ref "J2") (pin "4") (pinfunction "4_4") (pintype "passive+no_connect"))
    )
    (net (code "75") (name "unconnected-(U5-N.C.-Pad4)") (class "Default")
      (node (ref "U5") (pin "4") (pinfunction "N.C._4") (pintype "passive+no_connect"))
    )
    (net (code "76") (name "unconnected-(U6-NC-Pad2)") (class "Default")
      (node (ref "U6") (pin "2") (pinfunction "NC_2") (pintype "passive+no_connect"))
    )
    (net (code "77") (name "unconnected-(U6-NC-Pad3)") (class "Default")
      (node (ref "U6") (pin "3") (pinfunction "NC_3") (pintype "passive+no_connect"))
    )
    (net (code "78") (name "unconnected-(U6-NC-Pad4)") (class "Default")
      (node (ref "U6") (pin "4") (pinfunction "NC_4") (pintype "passive+no_connect"))
    )
    (net (code "79") (name "unconnected-(U9-NC-Pad3)") (class "Default")
      (node (ref "U9") (pin "3") (pinfunction "NC_3") (pintype "passive+no_connect"))
    )
    (net (code "80") (name "unconnected-(U9-NC-Pad4)") (class "Default")
      (node (ref "U9") (pin "4") (pinfunction "NC_4") (pintype "passive+no_connect"))
    )
    (net (code "81") (name "unconnected-(U29-NC-Pad3)") (class "Default")
      (node (ref "U29") (pin "3") (pinfunction "NC_3") (pintype "passive+no_connect"))
    )
    (net (code "82") (name "unconnected-(U29-NC-Pad4)") (class "Default")
      (node (ref "U29") (pin "4") (pinfunction "NC_4") (pintype "passive+no_connect"))
    )
  )
)
